# zx81_SD_12_smd_build002.net
KiCad netlist of a schematic drawn in EAGLE
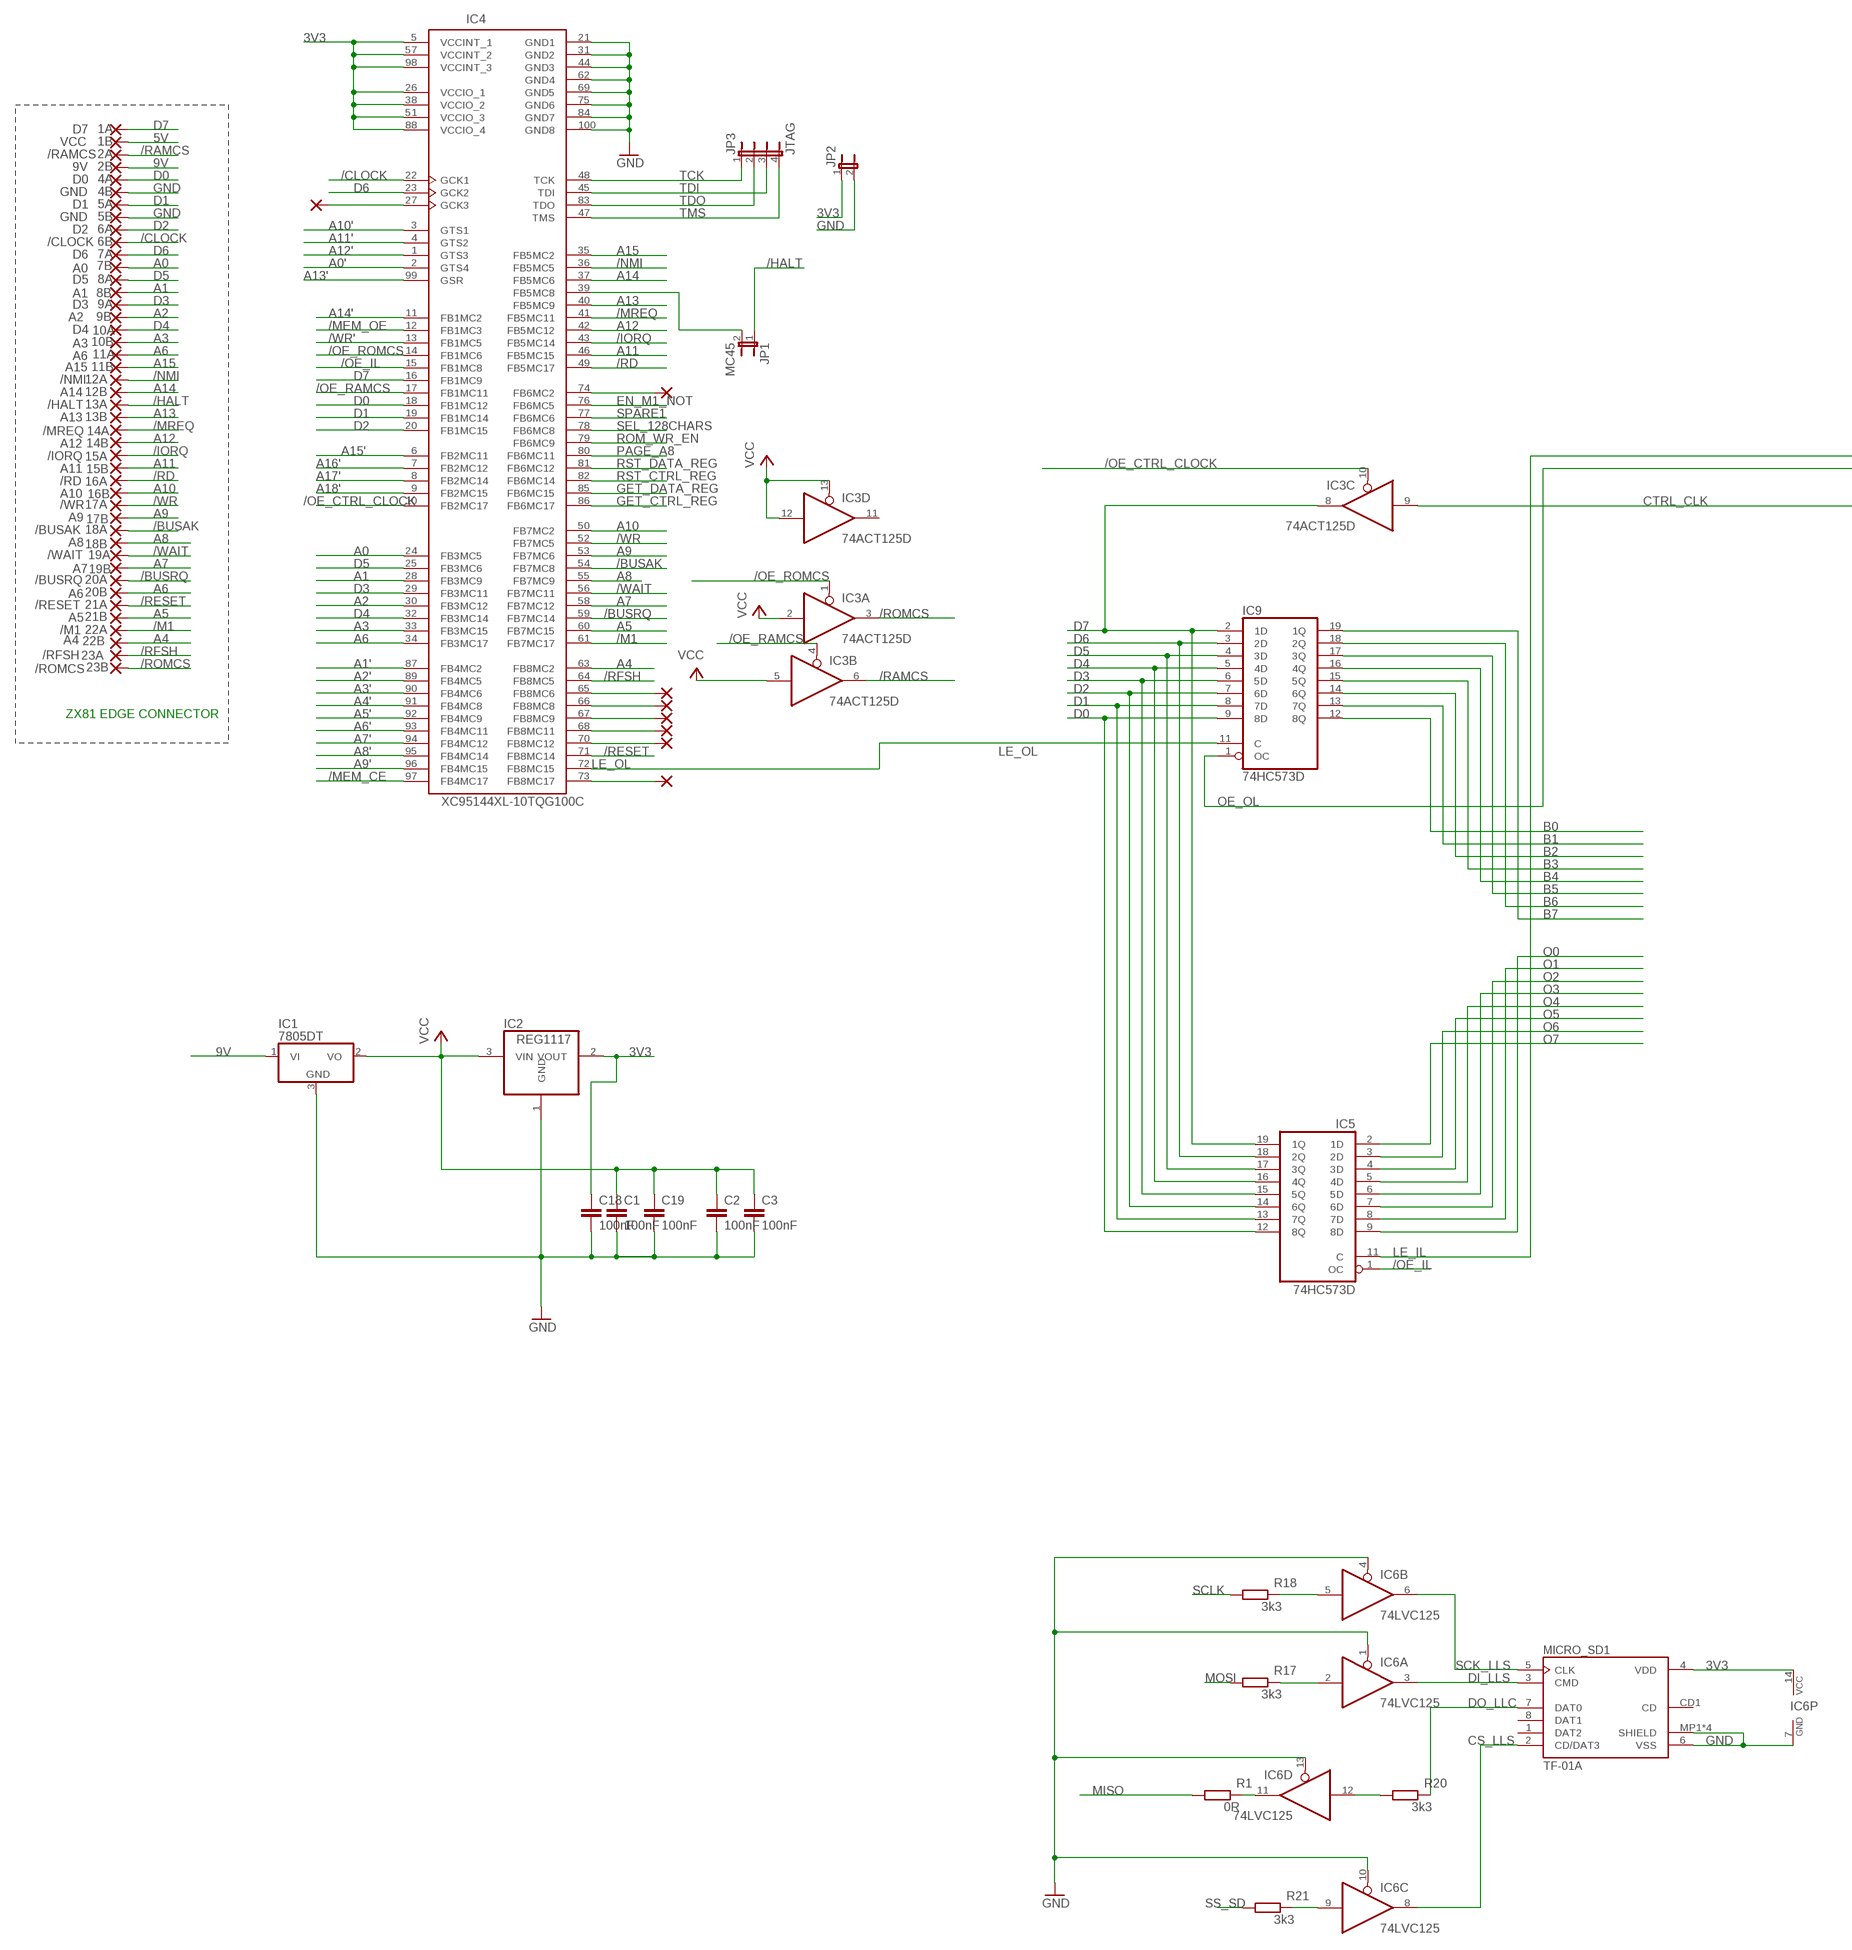
[diagram p0: schematic, sheet 1, part 1 of 2]
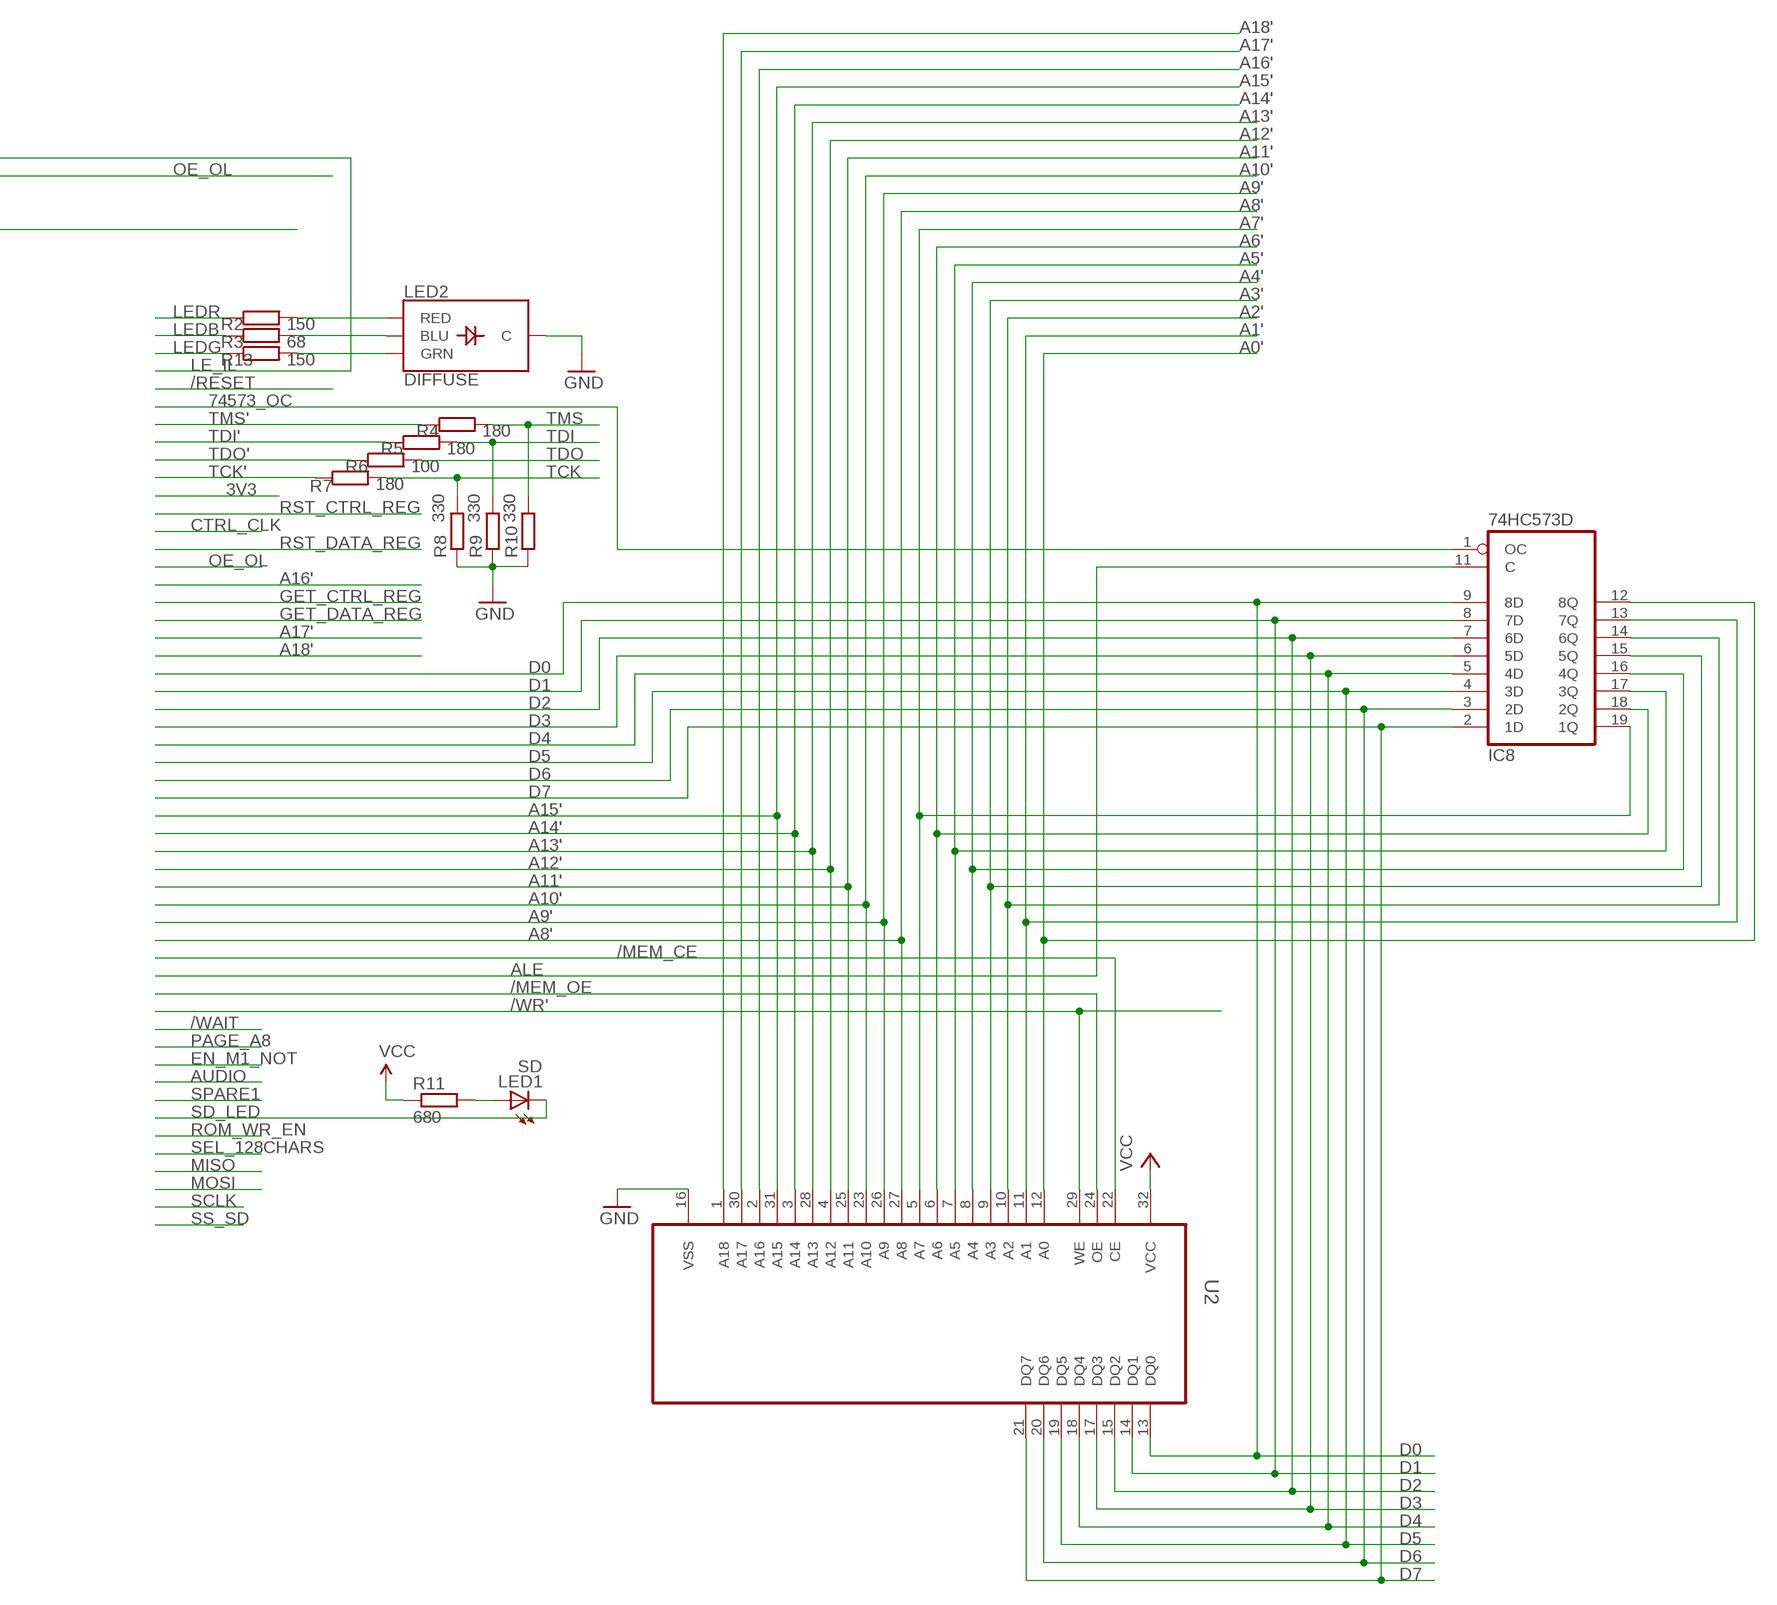
[diagram p1: schematic, sheet 1, part 2 of 2]
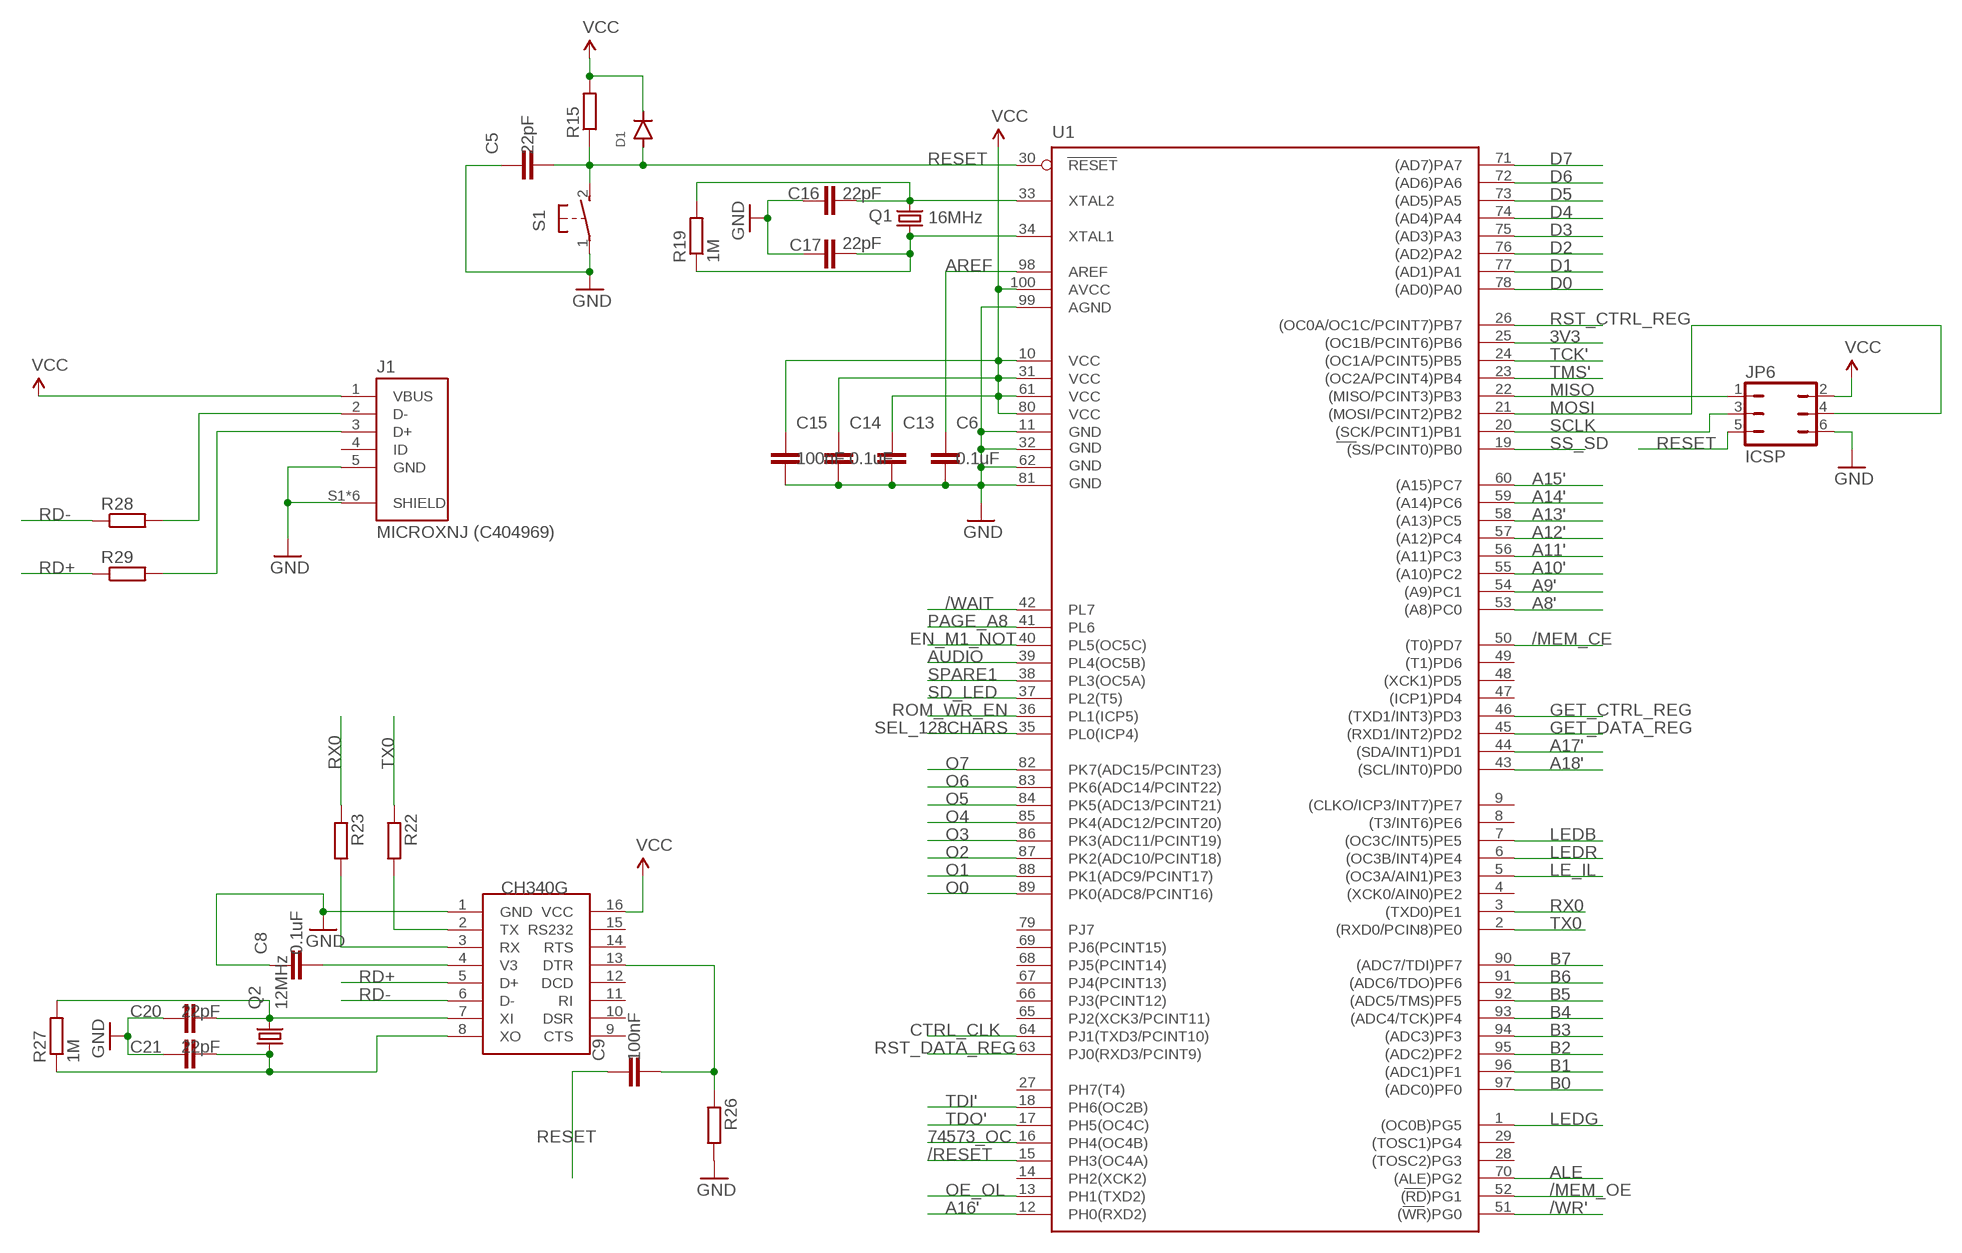
[diagram p2: schematic, sheet 2]

(export (version "E")
  (design (tool "Eeschema 10.0.6"))
  (components
    (comp (ref "C5")
      (value "22pF")
      (footprint "eagle-import:C0603")
      (libsource (lib "eagle-import") (part "C-EUC0603"))
    )
    (comp (ref "C6")
      (value "0.1uF")
      (footprint "eagle-import:C0603")
      (libsource (lib "eagle-import") (part "C-EUC0603"))
    )
    (comp (ref "C8")
      (value "0.1uF")
      (footprint "eagle-import:C0603")
      (libsource (lib "eagle-import") (part "C-EUC0603"))
    )
    (comp (ref "C9")
      (value "100nF")
      (footprint "eagle-import:C0603")
      (libsource (lib "eagle-import") (part "C-EUC0603"))
    )
    (comp (ref "C13")
      (value "0.1uF")
      (footprint "eagle-import:C0603")
      (libsource (lib "eagle-import") (part "C-EUC0603"))
    )
    (comp (ref "C14")
      (value "0.1uF")
      (footprint "eagle-import:C0603")
      (libsource (lib "eagle-import") (part "C-EUC0603"))
    )
    (comp (ref "C15")
      (value "100nF")
      (footprint "eagle-import:C0603")
      (libsource (lib "eagle-import") (part "C-EUC0603"))
    )
    (comp (ref "C16")
      (value "22pF")
      (footprint "eagle-import:C0603")
      (libsource (lib "eagle-import") (part "C-EUC0603"))
    )
    (comp (ref "C17")
      (value "22pF")
      (footprint "eagle-import:C0603")
      (libsource (lib "eagle-import") (part "C-EUC0603"))
    )
    (comp (ref "C20")
      (value "22pF")
      (footprint "eagle-import:C0603")
      (libsource (lib "eagle-import") (part "C-EUC0603"))
    )
    (comp (ref "C21")
      (value "22pF")
      (footprint "eagle-import:C0603")
      (libsource (lib "eagle-import") (part "C-EUC0603"))
    )
    (comp (ref "D1")
      (value "DIODE-SOD123")
      (footprint "eagle-import:SOD123")
      (libsource (lib "eagle-import") (part "DIODE-SOD123"))
    )
    (comp (ref "IC7")
      (value "CH340G")
      (footprint "eagle-import:SOIC16")
      (libsource (lib "eagle-import") (part "CH340G"))
    )
    (comp (ref "J1")
      (value "MICROXNJ (C404969)")
      (footprint "eagle-import:SHOUHAN_MICROXNJ")
      (fields (field (name "MF") "Shouhan") (field (name "MP") "MICROXNJ"))
      (libsource (lib "eagle-import") (part "MICROXNJ"))
    )
    (comp (ref "JP6")
      (value "ICSP")
      (footprint "eagle-import:JP3Q")
      (libsource (lib "eagle-import") (part "JP3Q"))
    )
    (comp (ref "Q1")
      (value "16MHz")
      (footprint "eagle-import:3.2X2.5_KX-7")
      (libsource (lib "eagle-import") (part "KX-7"))
    )
    (comp (ref "Q2")
      (value "12MHz")
      (footprint "eagle-import:3.2X2.5_KX-7")
      (libsource (lib "eagle-import") (part "KX-7"))
    )
    (comp (ref "R15")
      (value "R-EU_R0603")
      (footprint "eagle-import:R0603")
      (libsource (lib "eagle-import") (part "rcl_334_R-EU_R0603"))
    )
    (comp (ref "R19")
      (value "1M")
      (footprint "eagle-import:R0603")
      (libsource (lib "eagle-import") (part "rcl_334_R-EU_R0603"))
    )
    (comp (ref "R22")
      (value "1K")
      (footprint "eagle-import:R0603")
      (libsource (lib "eagle-import") (part "rcl_334_R-EU_R0603"))
    )
    (comp (ref "R23")
      (value "1K")
      (footprint "eagle-import:R0603")
      (libsource (lib "eagle-import") (part "rcl_334_R-EU_R0603"))
    )
    (comp (ref "R26")
      (value "1K")
      (footprint "eagle-import:R0603")
      (libsource (lib "eagle-import") (part "rcl_334_R-EU_R0603"))
    )
    (comp (ref "R27")
      (value "1M")
      (footprint "eagle-import:R0603")
      (libsource (lib "eagle-import") (part "rcl_334_R-EU_R0603"))
    )
    (comp (ref "R28")
      (value "22R")
      (footprint "eagle-import:R0603")
      (libsource (lib "eagle-import") (part "rcl_334_R-EU_R0603"))
    )
    (comp (ref "R29")
      (value "22R")
      (footprint "eagle-import:R0603")
      (libsource (lib "eagle-import") (part "rcl_334_R-EU_R0603"))
    )
    (comp (ref "S1")
      (value "31-XX")
      (footprint "eagle-import:B3F-31XX")
      (fields (field (name "MPN") "B3F-3100"))
      (libsource (lib "eagle-import") (part "31-XX"))
    )
    (comp (ref "U1")
      (value "ATMEGA2560AU")
      (footprint "eagle-import:TQFP100")
      (libsource (lib "eagle-import") (part "ATMEGA2560AU"))
    )
    (comp (ref "1A")
      (value "D7")
      (footprint "eagle-import:EDGEPIN")
      (libsource (lib "eagle-import") (part "SMD2EDGEPIN"))
    )
    (comp (ref "1B")
      (value "VCC")
      (footprint "eagle-import:EDGEPIN")
      (libsource (lib "eagle-import") (part "SMD2EDGEPIN"))
    )
    (comp (ref "2A")
      (value "/RAMCS")
      (footprint "eagle-import:EDGEPIN")
      (libsource (lib "eagle-import") (part "SMD2EDGEPIN"))
    )
    (comp (ref "2B")
      (value "9V")
      (footprint "eagle-import:EDGEPIN")
      (libsource (lib "eagle-import") (part "SMD2EDGEPIN"))
    )
    (comp (ref "4A")
      (value "D0")
      (footprint "eagle-import:EDGEPIN")
      (libsource (lib "eagle-import") (part "SMD2EDGEPIN"))
    )
    (comp (ref "4B")
      (value "GND")
      (footprint "eagle-import:EDGEPIN")
      (libsource (lib "eagle-import") (part "SMD2EDGEPIN"))
    )
    (comp (ref "5A")
      (value "D1")
      (footprint "eagle-import:EDGEPIN")
      (libsource (lib "eagle-import") (part "SMD2EDGEPIN"))
    )
    (comp (ref "5B")
      (value "GND")
      (footprint "eagle-import:EDGEPIN")
      (libsource (lib "eagle-import") (part "SMD2EDGEPIN"))
    )
    (comp (ref "6A")
      (value "D2")
      (footprint "eagle-import:EDGEPIN")
      (libsource (lib "eagle-import") (part "SMD2EDGEPIN"))
    )
    (comp (ref "6B")
      (value "/CLOCK")
      (footprint "eagle-import:EDGEPIN")
      (libsource (lib "eagle-import") (part "SMD2EDGEPIN"))
    )
    (comp (ref "7A")
      (value "D6")
      (footprint "eagle-import:EDGEPIN")
      (libsource (lib "eagle-import") (part "SMD2EDGEPIN"))
    )
    (comp (ref "7B")
      (value "A0")
      (footprint "eagle-import:EDGEPIN")
      (libsource (lib "eagle-import") (part "SMD2EDGEPIN"))
    )
    (comp (ref "8A")
      (value "D5")
      (footprint "eagle-import:EDGEPIN")
      (libsource (lib "eagle-import") (part "SMD2EDGEPIN"))
    )
    (comp (ref "8B")
      (value "A1")
      (footprint "eagle-import:EDGEPIN")
      (libsource (lib "eagle-import") (part "SMD2EDGEPIN"))
    )
    (comp (ref "9A")
      (value "D3")
      (footprint "eagle-import:EDGEPIN")
      (libsource (lib "eagle-import") (part "SMD2EDGEPIN"))
    )
    (comp (ref "9B")
      (value "A2")
      (footprint "eagle-import:EDGEPIN")
      (libsource (lib "eagle-import") (part "SMD2EDGEPIN"))
    )
    (comp (ref "10A")
      (value "D4")
      (footprint "eagle-import:EDGEPIN")
      (libsource (lib "eagle-import") (part "SMD2EDGEPIN"))
    )
    (comp (ref "10B")
      (value "A3")
      (footprint "eagle-import:EDGEPIN")
      (libsource (lib "eagle-import") (part "SMD2EDGEPIN"))
    )
    (comp (ref "11A")
      (value "A6")
      (footprint "eagle-import:EDGEPIN")
      (libsource (lib "eagle-import") (part "SMD2EDGEPIN"))
    )
    (comp (ref "11B")
      (value "A15")
      (footprint "eagle-import:EDGEPIN")
      (libsource (lib "eagle-import") (part "SMD2EDGEPIN"))
    )
    (comp (ref "12A")
      (value "/NMI")
      (footprint "eagle-import:EDGEPIN")
      (libsource (lib "eagle-import") (part "SMD2EDGEPIN"))
    )
    (comp (ref "12B")
      (value "A14")
      (footprint "eagle-import:EDGEPIN")
      (libsource (lib "eagle-import") (part "SMD2EDGEPIN"))
    )
    (comp (ref "13A")
      (value "/HALT")
      (footprint "eagle-import:EDGEPIN")
      (libsource (lib "eagle-import") (part "SMD2EDGEPIN"))
    )
    (comp (ref "13B")
      (value "A13")
      (footprint "eagle-import:EDGEPIN")
      (libsource (lib "eagle-import") (part "SMD2EDGEPIN"))
    )
    (comp (ref "14A")
      (value "/MREQ")
      (footprint "eagle-import:EDGEPIN")
      (libsource (lib "eagle-import") (part "SMD2EDGEPIN"))
    )
    (comp (ref "14B")
      (value "A12")
      (footprint "eagle-import:EDGEPIN")
      (libsource (lib "eagle-import") (part "SMD2EDGEPIN"))
    )
    (comp (ref "15A")
      (value "/IORQ")
      (footprint "eagle-import:EDGEPIN")
      (libsource (lib "eagle-import") (part "SMD2EDGEPIN"))
    )
    (comp (ref "15B")
      (value "A11")
      (footprint "eagle-import:EDGEPIN")
      (libsource (lib "eagle-import") (part "SMD2EDGEPIN"))
    )
    (comp (ref "16A")
      (value "/RD")
      (footprint "eagle-import:EDGEPIN")
      (libsource (lib "eagle-import") (part "SMD2EDGEPIN"))
    )
    (comp (ref "16B")
      (value "A10")
      (footprint "eagle-import:EDGEPIN")
      (libsource (lib "eagle-import") (part "SMD2EDGEPIN"))
    )
    (comp (ref "17A")
      (value "/WR")
      (footprint "eagle-import:EDGEPIN")
      (libsource (lib "eagle-import") (part "SMD2EDGEPIN"))
    )
    (comp (ref "17B")
      (value "A9")
      (footprint "eagle-import:EDGEPIN")
      (libsource (lib "eagle-import") (part "SMD2EDGEPIN"))
    )
    (comp (ref "18A")
      (value "/BUSAK")
      (footprint "eagle-import:EDGEPIN")
      (libsource (lib "eagle-import") (part "SMD2EDGEPIN"))
    )
    (comp (ref "18B")
      (value "A8")
      (footprint "eagle-import:EDGEPIN")
      (libsource (lib "eagle-import") (part "SMD2EDGEPIN"))
    )
    (comp (ref "19A")
      (value "/WAIT")
      (footprint "eagle-import:EDGEPIN")
      (libsource (lib "eagle-import") (part "SMD2EDGEPIN"))
    )
    (comp (ref "19B")
      (value "A7")
      (footprint "eagle-import:EDGEPIN")
      (libsource (lib "eagle-import") (part "SMD2EDGEPIN"))
    )
    (comp (ref "20A")
      (value "/BUSRQ")
      (footprint "eagle-import:EDGEPIN")
      (libsource (lib "eagle-import") (part "SMD2EDGEPIN"))
    )
    (comp (ref "20B")
      (value "A6")
      (footprint "eagle-import:EDGEPIN")
      (libsource (lib "eagle-import") (part "SMD2EDGEPIN"))
    )
    (comp (ref "21A")
      (value "/RESET")
      (footprint "eagle-import:EDGEPIN")
      (libsource (lib "eagle-import") (part "SMD2EDGEPIN"))
    )
    (comp (ref "21B")
      (value "A5")
      (footprint "eagle-import:EDGEPIN")
      (libsource (lib "eagle-import") (part "SMD2EDGEPIN"))
    )
    (comp (ref "22A")
      (value "/M1")
      (footprint "eagle-import:EDGEPIN")
      (libsource (lib "eagle-import") (part "SMD2EDGEPIN"))
    )
    (comp (ref "22B")
      (value "A4")
      (footprint "eagle-import:EDGEPIN")
      (libsource (lib "eagle-import") (part "SMD2EDGEPIN"))
    )
    (comp (ref "23A")
      (value "/RFSH")
      (footprint "eagle-import:EDGEPIN")
      (libsource (lib "eagle-import") (part "SMD2EDGEPIN"))
    )
    (comp (ref "23B")
      (value "/ROMCS")
      (footprint "eagle-import:EDGEPIN")
      (libsource (lib "eagle-import") (part "SMD2EDGEPIN"))
    )
    (comp (ref "C1")
      (value "100nF")
      (footprint "eagle-import:C0603")
      (libsource (lib "eagle-import") (part "C-EUC0603"))
    )
    (comp (ref "C2")
      (value "100nF")
      (footprint "eagle-import:C0603")
      (libsource (lib "eagle-import") (part "C-EUC0603"))
    )
    (comp (ref "C3")
      (value "100nF")
      (footprint "eagle-import:C0603")
      (libsource (lib "eagle-import") (part "C-EUC0603"))
    )
    (comp (ref "C18")
      (value "100nF")
      (footprint "eagle-import:C0603")
      (libsource (lib "eagle-import") (part "C-EUC0603"))
    )
    (comp (ref "C19")
      (value "100nF")
      (footprint "eagle-import:C0603")
      (libsource (lib "eagle-import") (part "C-EUC0603"))
    )
    (comp (ref "IC1")
      (value "7805DT")
      (footprint "eagle-import:TO252")
      (libsource (lib "eagle-import") (part "78DT05"))
    )
    (comp (ref "IC2")
      (value "REG1117")
      (footprint "eagle-import:SOT223")
      (libsource (lib "eagle-import") (part "REG1117"))
    )
    (comp (ref "IC3")
      (value "74ACT125D")
      (footprint "eagle-import:SO14")
      (libsource (lib "eagle-import") (part "74125DACT"))
    )
    (comp (ref "IC4")
      (value "XC95144XL-10TQG100C")
      (footprint "eagle-import:TQFP100")
      (fields (field (name "MF") "Xilinx Inc."))
      (libsource (lib "eagle-import") (part "XC95144XL-10TQG100C"))
    )
    (comp (ref "IC5")
      (value "74HC573D")
      (footprint "eagle-import:SO20W")
      (libsource (lib "eagle-import") (part "74573DHC"))
    )
    (comp (ref "IC6")
      (value "74LVC125")
      (footprint "eagle-import:SO14")
      (libsource (lib "eagle-import") (part "74125DLS"))
    )
    (comp (ref "IC8")
      (value "74HC573D")
      (footprint "eagle-import:SO20W")
      (libsource (lib "eagle-import") (part "74573DHC"))
    )
    (comp (ref "IC9")
      (value "74HC573D")
      (footprint "eagle-import:SO20W")
      (libsource (lib "eagle-import") (part "74573DHC"))
    )
    (comp (ref "JP1")
      (value "MC45")
      (footprint "eagle-import:JP1")
      (libsource (lib "eagle-import") (part "JP1E"))
    )
    (comp (ref "JP2")
      (value "JP1E")
      (footprint "eagle-import:JP1")
      (libsource (lib "eagle-import") (part "JP1E"))
    )
    (comp (ref "JP3")
      (value "JTAG")
      (footprint "eagle-import:JP4")
      (libsource (lib "eagle-import") (part "JP4E"))
    )
    (comp (ref "LED1")
      (value "SD")
      (footprint "eagle-import:LED5MM")
      (libsource (lib "eagle-import") (part "LED5MM"))
    )
    (comp (ref "LED2")
      (value "DIFFUSE")
      (footprint "eagle-import:LED-RGB-THRU")
      (libsource (lib "eagle-import") (part "LED-RGB-CCDIFFUSE"))
    )
    (comp (ref "MICRO_SD1")
      (value "TF-01A")
      (footprint "eagle-import:TF-01A")
      (fields (field (name "MF") "HRO Electronics Co., Ltd."))
      (libsource (lib "eagle-import") (part "TF-01A"))
    )
    (comp (ref "PAD1")
      (value "1,6/0,8")
      (footprint "eagle-import:1,6_0,8")
      (libsource (lib "eagle-import") (part "1,6/0,8"))
    )
    (comp (ref "PAD2")
      (value "1,6/0,8")
      (footprint "eagle-import:1,6_0,8")
      (libsource (lib "eagle-import") (part "1,6/0,8"))
    )
    (comp (ref "PAD3")
      (value "1,6/0,8")
      (footprint "eagle-import:1,6_0,8")
      (libsource (lib "eagle-import") (part "1,6/0,8"))
    )
    (comp (ref "PAD4")
      (value "1,6/0,8")
      (footprint "eagle-import:1,6_0,8")
      (libsource (lib "eagle-import") (part "1,6/0,8"))
    )
    (comp (ref "PAD5")
      (value "1,6/0,8")
      (footprint "eagle-import:1,6_0,8")
      (libsource (lib "eagle-import") (part "1,6/0,8"))
    )
    (comp (ref "PAD6")
      (value "1,6/0,8")
      (footprint "eagle-import:1,6_0,8")
      (libsource (lib "eagle-import") (part "1,6/0,8"))
    )
    (comp (ref "PAD7")
      (value "1,6/0,8")
      (footprint "eagle-import:1,6_0,8")
      (libsource (lib "eagle-import") (part "1,6/0,8"))
    )
    (comp (ref "PAD8")
      (value "1,6/0,8")
      (footprint "eagle-import:1,6_0,8")
      (libsource (lib "eagle-import") (part "1,6/0,8"))
    )
    (comp (ref "R1")
      (value "0R")
      (footprint "eagle-import:R0603")
      (libsource (lib "eagle-import") (part "R-EU_R0603"))
    )
    (comp (ref "R2")
      (value "150")
      (footprint "eagle-import:R0603")
      (libsource (lib "eagle-import") (part "rcl_334_R-EU_R0603"))
    )
    (comp (ref "R3")
      (value "68")
      (footprint "eagle-import:R0603")
      (libsource (lib "eagle-import") (part "rcl_334_R-EU_R0603"))
    )
    (comp (ref "R4")
      (value "180")
      (footprint "eagle-import:R0603")
      (libsource (lib "eagle-import") (part "rcl_334_R-EU_R0603"))
    )
    (comp (ref "R5")
      (value "180")
      (footprint "eagle-import:R0603")
      (libsource (lib "eagle-import") (part "rcl_334_R-EU_R0603"))
    )
    (comp (ref "R6")
      (value "100")
      (footprint "eagle-import:R0603")
      (libsource (lib "eagle-import") (part "rcl_334_R-EU_R0603"))
    )
    (comp (ref "R7")
      (value "180")
      (footprint "eagle-import:R0603")
      (libsource (lib "eagle-import") (part "rcl_334_R-EU_R0603"))
    )
    (comp (ref "R8")
      (value "330")
      (footprint "eagle-import:R0603")
      (libsource (lib "eagle-import") (part "rcl_334_R-EU_R0603"))
    )
    (comp (ref "R9")
      (value "330")
      (footprint "eagle-import:R0603")
      (libsource (lib "eagle-import") (part "rcl_334_R-EU_R0603"))
    )
    (comp (ref "R10")
      (value "330")
      (footprint "eagle-import:R0603")
      (libsource (lib "eagle-import") (part "rcl_334_R-EU_R0603"))
    )
    (comp (ref "R11")
      (value "680")
      (footprint "eagle-import:R0603")
      (libsource (lib "eagle-import") (part "R-EU_R0603"))
    )
    (comp (ref "R13")
      (value "150")
      (footprint "eagle-import:R0603")
      (libsource (lib "eagle-import") (part "rcl_334_R-EU_R0603"))
    )
    (comp (ref "R17")
      (value "3k3")
      (footprint "eagle-import:R0603")
      (libsource (lib "eagle-import") (part "R-EU_R0603"))
    )
    (comp (ref "R18")
      (value "3k3")
      (footprint "eagle-import:R0603")
      (libsource (lib "eagle-import") (part "R-EU_R0603"))
    )
    (comp (ref "R20")
      (value "3k3")
      (footprint "eagle-import:R0603")
      (libsource (lib "eagle-import") (part "R-EU_R0603"))
    )
    (comp (ref "R21")
      (value "3k3")
      (footprint "eagle-import:R0603")
      (libsource (lib "eagle-import") (part "R-EU_R0603"))
    )
    (comp (ref "U2")
      (value "AS6C4008-55SINSOP5")
      (footprint "eagle-import:SOP32-5")
      (libsource (lib "eagle-import") (part "AS6C4008-55SINSOP5"))
    )
  )
  (nets
    (net (code "1") (name "3V3") (class "Default")
      (node (ref "C18") (pin "1") (pinfunction "1_1") (pintype "passive"))
      (node (ref "IC2") (pin "2") (pinfunction "VOUT_2") (pintype "output"))
      (node (ref "IC4") (pin "26") (pinfunction "VCCIO_1_26") (pintype "power_in"))
      (node (ref "IC4") (pin "38") (pinfunction "VCCIO_2_38") (pintype "power_in"))
      (node (ref "IC4") (pin "5") (pinfunction "VCCINT_1_5") (pintype "power_in"))
      (node (ref "IC4") (pin "51") (pinfunction "VCCIO_3_51") (pintype "power_in"))
      (node (ref "IC4") (pin "57") (pinfunction "VCCINT_2_57") (pintype "power_in"))
      (node (ref "IC4") (pin "88") (pinfunction "VCCIO_4_88") (pintype "power_in"))
      (node (ref "IC4") (pin "98") (pinfunction "VCCINT_3_98") (pintype "power_in"))
      (node (ref "IC6") (pin "14") (pinfunction "VCC_14") (pintype "power_in"))
      (node (ref "JP2") (pin "1") (pinfunction "1_1") (pintype "passive"))
      (node (ref "MICRO_SD1") (pin "4") (pinfunction "VDD_4") (pintype "power_in"))
      (node (ref "U1") (pin "25") (pinfunction "(OC1B/PCINT6)PB6_25") (pintype "bidirectional"))
    )
    (net (code "2") (name "5V") (class "Default")
      (node (ref "1B") (pin "1") (pinfunction "P_1") (pintype "passive"))
    )
    (net (code "3") (name "9V") (class "Default")
      (node (ref "2B") (pin "1") (pinfunction "P_1") (pintype "passive"))
      (node (ref "IC1") (pin "1") (pinfunction "VI_1") (pintype "input"))
    )
    (net (code "4") (name "74573_OC") (class "Default")
      (node (ref "IC8") (pin "1") (pinfunction "OC_1") (pintype "input"))
      (node (ref "U1") (pin "16") (pinfunction "PH4(OC4B)_16") (pintype "bidirectional"))
    )
    (net (code "5") (name "A0") (class "Default")
      (node (ref "7B") (pin "1") (pinfunction "P_1") (pintype "passive"))
      (node (ref "IC4") (pin "24") (pinfunction "FB3MC5_24") (pintype "bidirectional"))
    )
    (net (code "6") (name "A0'") (class "Default")
      (node (ref "IC4") (pin "2") (pinfunction "GTS4_2") (pintype "bidirectional"))
      (node (ref "IC8") (pin "12") (pinfunction "8Q_12") (pintype "tri_state"))
      (node (ref "U2") (pin "12") (pinfunction "A0_12") (pintype "input"))
    )
    (net (code "7") (name "A1") (class "Default")
      (node (ref "8B") (pin "1") (pinfunction "P_1") (pintype "passive"))
      (node (ref "IC4") (pin "28") (pinfunction "FB3MC9_28") (pintype "bidirectional"))
    )
    (net (code "8") (name "A1'") (class "Default")
      (node (ref "IC4") (pin "87") (pinfunction "FB4MC2_87") (pintype "bidirectional"))
      (node (ref "IC8") (pin "13") (pinfunction "7Q_13") (pintype "tri_state"))
      (node (ref "U2") (pin "11") (pinfunction "A1_11") (pintype "input"))
    )
    (net (code "9") (name "A2") (class "Default")
      (node (ref "9B") (pin "1") (pinfunction "P_1") (pintype "passive"))
      (node (ref "IC4") (pin "30") (pinfunction "FB3MC12_30") (pintype "bidirectional"))
    )
    (net (code "10") (name "A2'") (class "Default")
      (node (ref "IC4") (pin "89") (pinfunction "FB4MC5_89") (pintype "bidirectional"))
      (node (ref "IC8") (pin "14") (pinfunction "6Q_14") (pintype "tri_state"))
      (node (ref "U2") (pin "10") (pinfunction "A2_10") (pintype "input"))
    )
    (net (code "11") (name "A3") (class "Default")
      (node (ref "10B") (pin "1") (pinfunction "P_1") (pintype "passive"))
      (node (ref "IC4") (pin "33") (pinfunction "FB3MC15_33") (pintype "bidirectional"))
    )
    (net (code "12") (name "A3'") (class "Default")
      (node (ref "IC4") (pin "90") (pinfunction "FB4MC6_90") (pintype "bidirectional"))
      (node (ref "IC8") (pin "15") (pinfunction "5Q_15") (pintype "tri_state"))
      (node (ref "U2") (pin "9") (pinfunction "A3_9") (pintype "input"))
    )
    (net (code "13") (name "A4") (class "Default")
      (node (ref "22B") (pin "1") (pinfunction "P_1") (pintype "passive"))
      (node (ref "IC4") (pin "63") (pinfunction "FB8MC2_63") (pintype "bidirectional"))
    )
    (net (code "14") (name "A4'") (class "Default")
      (node (ref "IC4") (pin "91") (pinfunction "FB4MC8_91") (pintype "bidirectional"))
      (node (ref "IC8") (pin "16") (pinfunction "4Q_16") (pintype "tri_state"))
      (node (ref "U2") (pin "8") (pinfunction "A4_8") (pintype "input"))
    )
    (net (code "15") (name "A5") (class "Default")
      (node (ref "21B") (pin "1") (pinfunction "P_1") (pintype "passive"))
      (node (ref "IC4") (pin "60") (pinfunction "FB7MC15_60") (pintype "bidirectional"))
    )
    (net (code "16") (name "A5'") (class "Default")
      (node (ref "IC4") (pin "92") (pinfunction "FB4MC9_92") (pintype "bidirectional"))
      (node (ref "IC8") (pin "17") (pinfunction "3Q_17") (pintype "tri_state"))
      (node (ref "U2") (pin "7") (pinfunction "A5_7") (pintype "input"))
    )
    (net (code "17") (name "A6") (class "Default")
      (node (ref "11A") (pin "1") (pinfunction "P_1") (pintype "passive"))
      (node (ref "20B") (pin "1") (pinfunction "P_1") (pintype "passive"))
      (node (ref "IC4") (pin "34") (pinfunction "FB3MC17_34") (pintype "bidirectional"))
    )
    (net (code "18") (name "A6'") (class "Default")
      (node (ref "IC4") (pin "93") (pinfunction "FB4MC11_93") (pintype "bidirectional"))
      (node (ref "IC8") (pin "18") (pinfunction "2Q_18") (pintype "tri_state"))
      (node (ref "U2") (pin "6") (pinfunction "A6_6") (pintype "input"))
    )
    (net (code "19") (name "A7") (class "Default")
      (node (ref "19B") (pin "1") (pinfunction "P_1") (pintype "passive"))
      (node (ref "IC4") (pin "58") (pinfunction "FB7MC12_58") (pintype "bidirectional"))
    )
    (net (code "20") (name "A7'") (class "Default")
      (node (ref "IC4") (pin "94") (pinfunction "FB4MC12_94") (pintype "bidirectional"))
      (node (ref "IC8") (pin "19") (pinfunction "1Q_19") (pintype "tri_state"))
      (node (ref "U2") (pin "5") (pinfunction "A7_5") (pintype "input"))
    )
    (net (code "21") (name "A8") (class "Default")
      (node (ref "18B") (pin "1") (pinfunction "P_1") (pintype "passive"))
      (node (ref "IC4") (pin "55") (pinfunction "FB7MC9_55") (pintype "bidirectional"))
    )
    (net (code "22") (name "A8'") (class "Default")
      (node (ref "IC4") (pin "95") (pinfunction "FB4MC14_95") (pintype "bidirectional"))
      (node (ref "U1") (pin "53") (pinfunction "(A8)PC0_53") (pintype "bidirectional"))
      (node (ref "U2") (pin "27") (pinfunction "A8_27") (pintype "input"))
    )
    (net (code "23") (name "A9") (class "Default")
      (node (ref "17B") (pin "1") (pinfunction "P_1") (pintype "passive"))
      (node (ref "IC4") (pin "53") (pinfunction "FB7MC6_53") (pintype "bidirectional"))
    )
    (net (code "24") (name "A9'") (class "Default")
      (node (ref "IC4") (pin "96") (pinfunction "FB4MC15_96") (pintype "bidirectional"))
      (node (ref "U1") (pin "54") (pinfunction "(A9)PC1_54") (pintype "bidirectional"))
      (node (ref "U2") (pin "26") (pinfunction "A9_26") (pintype "input"))
    )
    (net (code "25") (name "A10") (class "Default")
      (node (ref "16B") (pin "1") (pinfunction "P_1") (pintype "passive"))
      (node (ref "IC4") (pin "50") (pinfunction "FB7MC2_50") (pintype "bidirectional"))
    )
    (net (code "26") (name "A10'") (class "Default")
      (node (ref "IC4") (pin "3") (pinfunction "GTS1_3") (pintype "bidirectional"))
      (node (ref "U1") (pin "55") (pinfunction "(A10)PC2_55") (pintype "bidirectional"))
      (node (ref "U2") (pin "23") (pinfunction "A10_23") (pintype "input"))
    )
    (net (code "27") (name "A11") (class "Default")
      (node (ref "15B") (pin "1") (pinfunction "P_1") (pintype "passive"))
      (node (ref "IC4") (pin "46") (pinfunction "FB5MC15_46") (pintype "bidirectional"))
    )
    (net (code "28") (name "A11'") (class "Default")
      (node (ref "IC4") (pin "4") (pinfunction "GTS2_4") (pintype "bidirectional"))
      (node (ref "U1") (pin "56") (pinfunction "(A11)PC3_56") (pintype "bidirectional"))
      (node (ref "U2") (pin "25") (pinfunction "A11_25") (pintype "input"))
    )
    (net (code "29") (name "A12") (class "Default")
      (node (ref "14B") (pin "1") (pinfunction "P_1") (pintype "passive"))
      (node (ref "IC4") (pin "42") (pinfunction "FB5MC12_42") (pintype "bidirectional"))
    )
    (net (code "30") (name "A12'") (class "Default")
      (node (ref "IC4") (pin "1") (pinfunction "GTS3_1") (pintype "bidirectional"))
      (node (ref "U1") (pin "57") (pinfunction "(A12)PC4_57") (pintype "bidirectional"))
      (node (ref "U2") (pin "4") (pinfunction "A12_4") (pintype "input"))
    )
    (net (code "31") (name "A13") (class "Default")
      (node (ref "13B") (pin "1") (pinfunction "P_1") (pintype "passive"))
      (node (ref "IC4") (pin "40") (pinfunction "FB5MC9_40") (pintype "bidirectional"))
    )
    (net (code "32") (name "A13'") (class "Default")
      (node (ref "IC4") (pin "99") (pinfunction "GSR_99") (pintype "bidirectional"))
      (node (ref "U1") (pin "58") (pinfunction "(A13)PC5_58") (pintype "bidirectional"))
      (node (ref "U2") (pin "28") (pinfunction "A13_28") (pintype "input"))
    )
    (net (code "33") (name "A14") (class "Default")
      (node (ref "12B") (pin "1") (pinfunction "P_1") (pintype "passive"))
      (node (ref "IC4") (pin "37") (pinfunction "FB5MC6_37") (pintype "bidirectional"))
    )
    (net (code "34") (name "A14'") (class "Default")
      (node (ref "IC4") (pin "11") (pinfunction "FB1MC2_11") (pintype "bidirectional"))
      (node (ref "U1") (pin "59") (pinfunction "(A14)PC6_59") (pintype "bidirectional"))
      (node (ref "U2") (pin "3") (pinfunction "A14_3") (pintype "input"))
    )
    (net (code "35") (name "A15") (class "Default")
      (node (ref "11B") (pin "1") (pinfunction "P_1") (pintype "passive"))
      (node (ref "IC4") (pin "35") (pinfunction "FB5MC2_35") (pintype "bidirectional"))
    )
    (net (code "36") (name "A15'") (class "Default")
      (node (ref "IC4") (pin "6") (pinfunction "FB2MC11_6") (pintype "bidirectional"))
      (node (ref "U1") (pin "60") (pinfunction "(A15)PC7_60") (pintype "bidirectional"))
      (node (ref "U2") (pin "31") (pinfunction "A15_31") (pintype "input"))
    )
    (net (code "37") (name "A16'") (class "Default")
      (node (ref "IC4") (pin "7") (pinfunction "FB2MC12_7") (pintype "bidirectional"))
      (node (ref "U1") (pin "12") (pinfunction "PH0(RXD2)_12") (pintype "bidirectional"))
      (node (ref "U2") (pin "2") (pinfunction "A16_2") (pintype "input"))
    )
    (net (code "38") (name "A17'") (class "Default")
      (node (ref "IC4") (pin "8") (pinfunction "FB2MC14_8") (pintype "bidirectional"))
      (node (ref "U1") (pin "44") (pinfunction "(SDA/INT1)PD1_44") (pintype "bidirectional"))
      (node (ref "U2") (pin "30") (pinfunction "A17_30") (pintype "input"))
    )
    (net (code "39") (name "A18'") (class "Default")
      (node (ref "IC4") (pin "9") (pinfunction "FB2MC15_9") (pintype "bidirectional"))
      (node (ref "U1") (pin "43") (pinfunction "(SCL/INT0)PD0_43") (pintype "bidirectional"))
      (node (ref "U2") (pin "1") (pinfunction "A18_1") (pintype "input"))
    )
    (net (code "40") (name "ALE") (class "Default")
      (node (ref "IC8") (pin "11") (pinfunction "C_11") (pintype "input"))
      (node (ref "U1") (pin "70") (pinfunction "(ALE)PG2_70") (pintype "bidirectional"))
    )
    (net (code "41") (name "AREF") (class "Default")
      (node (ref "C6") (pin "1") (pinfunction "1_1") (pintype "passive"))
      (node (ref "U1") (pin "98") (pinfunction "AREF_98") (pintype "bidirectional"))
    )
    (net (code "42") (name "AUDIO") (class "Default")
      (node (ref "U1") (pin "39") (pinfunction "PL4(OC5B)_39") (pintype "bidirectional"))
    )
    (net (code "43") (name "B0") (class "Default")
      (node (ref "IC9") (pin "19") (pinfunction "1Q_19") (pintype "tri_state"))
      (node (ref "U1") (pin "97") (pinfunction "(ADC0)PF0_97") (pintype "bidirectional"))
    )
    (net (code "44") (name "B1") (class "Default")
      (node (ref "IC9") (pin "18") (pinfunction "2Q_18") (pintype "tri_state"))
      (node (ref "U1") (pin "96") (pinfunction "(ADC1)PF1_96") (pintype "bidirectional"))
    )
    (net (code "45") (name "B2") (class "Default")
      (node (ref "IC9") (pin "17") (pinfunction "3Q_17") (pintype "tri_state"))
      (node (ref "U1") (pin "95") (pinfunction "(ADC2)PF2_95") (pintype "bidirectional"))
    )
    (net (code "46") (name "B3") (class "Default")
      (node (ref "IC9") (pin "16") (pinfunction "4Q_16") (pintype "tri_state"))
      (node (ref "U1") (pin "94") (pinfunction "(ADC3)PF3_94") (pintype "bidirectional"))
    )
    (net (code "47") (name "B4") (class "Default")
      (node (ref "IC9") (pin "15") (pinfunction "5Q_15") (pintype "tri_state"))
      (node (ref "U1") (pin "93") (pinfunction "(ADC4/TCK)PF4_93") (pintype "bidirectional"))
    )
    (net (code "48") (name "B5") (class "Default")
      (node (ref "IC9") (pin "14") (pinfunction "6Q_14") (pintype "tri_state"))
      (node (ref "U1") (pin "92") (pinfunction "(ADC5/TMS)PF5_92") (pintype "bidirectional"))
    )
    (net (code "49") (name "B6") (class "Default")
      (node (ref "IC9") (pin "13") (pinfunction "7Q_13") (pintype "tri_state"))
      (node (ref "U1") (pin "91") (pinfunction "(ADC6/TDO)PF6_91") (pintype "bidirectional"))
    )
    (net (code "50") (name "B7") (class "Default")
      (node (ref "IC9") (pin "12") (pinfunction "8Q_12") (pintype "tri_state"))
      (node (ref "U1") (pin "90") (pinfunction "(ADC7/TDI)PF7_90") (pintype "bidirectional"))
    )
    (net (code "51") (name "CS_LLS") (class "Default")
      (node (ref "IC6") (pin "8") (pinfunction "O_8") (pintype "tri_state"))
      (node (ref "MICRO_SD1") (pin "2") (pinfunction "CD/DAT3_2") (pintype "bidirectional"))
    )
    (net (code "52") (name "CTRL_CLK") (class "Default")
      (node (ref "IC3") (pin "9") (pinfunction "I_9") (pintype "input"))
      (node (ref "U1") (pin "64") (pinfunction "PJ1(TXD3/PCINT10)_64") (pintype "bidirectional"))
    )
    (net (code "53") (name "D0") (class "Default")
      (node (ref "4A") (pin "1") (pinfunction "P_1") (pintype "passive"))
      (node (ref "IC4") (pin "18") (pinfunction "FB1MC12_18") (pintype "bidirectional"))
      (node (ref "IC5") (pin "12") (pinfunction "8Q_12") (pintype "tri_state"))
      (node (ref "IC8") (pin "9") (pinfunction "8D_9") (pintype "input"))
      (node (ref "IC9") (pin "9") (pinfunction "8D_9") (pintype "input"))
      (node (ref "U1") (pin "78") (pinfunction "(AD0)PA0_78") (pintype "bidirectional"))
      (node (ref "U2") (pin "13") (pinfunction "DQ0_13") (pintype "output"))
    )
    (net (code "54") (name "D1") (class "Default")
      (node (ref "5A") (pin "1") (pinfunction "P_1") (pintype "passive"))
      (node (ref "IC4") (pin "19") (pinfunction "FB1MC14_19") (pintype "bidirectional"))
      (node (ref "IC5") (pin "13") (pinfunction "7Q_13") (pintype "tri_state"))
      (node (ref "IC8") (pin "8") (pinfunction "7D_8") (pintype "input"))
      (node (ref "IC9") (pin "8") (pinfunction "7D_8") (pintype "input"))
      (node (ref "U1") (pin "77") (pinfunction "(AD1)PA1_77") (pintype "bidirectional"))
      (node (ref "U2") (pin "14") (pinfunction "DQ1_14") (pintype "output"))
    )
    (net (code "55") (name "D2") (class "Default")
      (node (ref "6A") (pin "1") (pinfunction "P_1") (pintype "passive"))
      (node (ref "IC4") (pin "20") (pinfunction "FB1MC15_20") (pintype "bidirectional"))
      (node (ref "IC5") (pin "14") (pinfunction "6Q_14") (pintype "tri_state"))
      (node (ref "IC8") (pin "7") (pinfunction "6D_7") (pintype "input"))
      (node (ref "IC9") (pin "7") (pinfunction "6D_7") (pintype "input"))
      (node (ref "U1") (pin "76") (pinfunction "(AD2)PA2_76") (pintype "bidirectional"))
      (node (ref "U2") (pin "15") (pinfunction "DQ2_15") (pintype "output"))
    )
    (net (code "56") (name "D3") (class "Default")
      (node (ref "9A") (pin "1") (pinfunction "P_1") (pintype "passive"))
      (node (ref "IC4") (pin "29") (pinfunction "FB3MC11_29") (pintype "bidirectional"))
      (node (ref "IC5") (pin "15") (pinfunction "5Q_15") (pintype "tri_state"))
      (node (ref "IC8") (pin "6") (pinfunction "5D_6") (pintype "input"))
      (node (ref "IC9") (pin "6") (pinfunction "5D_6") (pintype "input"))
      (node (ref "U1") (pin "75") (pinfunction "(AD3)PA3_75") (pintype "bidirectional"))
      (node (ref "U2") (pin "17") (pinfunction "DQ3_17") (pintype "output"))
    )
    (net (code "57") (name "D4") (class "Default")
      (node (ref "10A") (pin "1") (pinfunction "P_1") (pintype "passive"))
      (node (ref "IC4") (pin "32") (pinfunction "FB3MC14_32") (pintype "bidirectional"))
      (node (ref "IC5") (pin "16") (pinfunction "4Q_16") (pintype "tri_state"))
      (node (ref "IC8") (pin "5") (pinfunction "4D_5") (pintype "input"))
      (node (ref "IC9") (pin "5") (pinfunction "4D_5") (pintype "input"))
      (node (ref "U1") (pin "74") (pinfunction "(AD4)PA4_74") (pintype "bidirectional"))
      (node (ref "U2") (pin "18") (pinfunction "DQ4_18") (pintype "output"))
    )
    (net (code "58") (name "D5") (class "Default")
      (node (ref "8A") (pin "1") (pinfunction "P_1") (pintype "passive"))
      (node (ref "IC4") (pin "25") (pinfunction "FB3MC6_25") (pintype "bidirectional"))
      (node (ref "IC5") (pin "17") (pinfunction "3Q_17") (pintype "tri_state"))
      (node (ref "IC8") (pin "4") (pinfunction "3D_4") (pintype "input"))
      (node (ref "IC9") (pin "4") (pinfunction "3D_4") (pintype "input"))
      (node (ref "U1") (pin "73") (pinfunction "(AD5)PA5_73") (pintype "bidirectional"))
      (node (ref "U2") (pin "19") (pinfunction "DQ5_19") (pintype "output"))
    )
    (net (code "59") (name "D6") (class "Default")
      (node (ref "7A") (pin "1") (pinfunction "P_1") (pintype "passive"))
      (node (ref "IC4") (pin "23") (pinfunction "GCK2_23") (pintype "bidirectional"))
      (node (ref "IC5") (pin "18") (pinfunction "2Q_18") (pintype "tri_state"))
      (node (ref "IC8") (pin "3") (pinfunction "2D_3") (pintype "input"))
      (node (ref "IC9") (pin "3") (pinfunction "2D_3") (pintype "input"))
      (node (ref "U1") (pin "72") (pinfunction "(AD6)PA6_72") (pintype "bidirectional"))
      (node (ref "U2") (pin "20") (pinfunction "DQ6_20") (pintype "output"))
    )
    (net (code "60") (name "D7") (class "Default")
      (node (ref "1A") (pin "1") (pinfunction "P_1") (pintype "passive"))
      (node (ref "IC3") (pin "8") (pinfunction "O_8") (pintype "tri_state"))
      (node (ref "IC4") (pin "16") (pinfunction "FB1MC9_16") (pintype "bidirectional"))
      (node (ref "IC5") (pin "19") (pinfunction "1Q_19") (pintype "tri_state"))
      (node (ref "IC8") (pin "2") (pinfunction "1D_2") (pintype "input"))
      (node (ref "IC9") (pin "2") (pinfunction "1D_2") (pintype "input"))
      (node (ref "U1") (pin "71") (pinfunction "(AD7)PA7_71") (pintype "bidirectional"))
      (node (ref "U2") (pin "21") (pinfunction "DQ7_21") (pintype "output"))
    )
    (net (code "61") (name "DI_LLS") (class "Default")
      (node (ref "IC6") (pin "3") (pinfunction "O_3") (pintype "tri_state"))
      (node (ref "MICRO_SD1") (pin "3") (pinfunction "CMD_3") (pintype "bidirectional"))
    )
    (net (code "62") (name "DO_LLC") (class "Default")
      (node (ref "IC6") (pin "12") (pinfunction "I_12") (pintype "input"))
      (node (ref "R20") (pin "1") (pinfunction "1_1") (pintype "passive"))
    )
    (net (code "63") (name "EN_M1_NOT") (class "Default")
      (node (ref "IC4") (pin "76") (pinfunction "FB6MC5_76") (pintype "bidirectional"))
      (node (ref "U1") (pin "40") (pinfunction "PL5(OC5C)_40") (pintype "bidirectional"))
    )
    (net (code "64") (name "GET_CTRL_REG") (class "Default")
      (node (ref "IC4") (pin "86") (pinfunction "FB6MC17_86") (pintype "bidirectional"))
      (node (ref "U1") (pin "46") (pinfunction "(TXD1/INT3)PD3_46") (pintype "bidirectional"))
    )
    (net (code "65") (name "GET_DATA_REG") (class "Default")
      (node (ref "IC4") (pin "85") (pinfunction "FB6MC15_85") (pintype "bidirectional"))
      (node (ref "U1") (pin "45") (pinfunction "(RXD1/INT2)PD2_45") (pintype "bidirectional"))
    )
    (net (code "66") (name "GND") (class "Default")
      (node (ref "4B") (pin "1") (pinfunction "P_1") (pintype "passive"))
      (node (ref "5B") (pin "1") (pinfunction "P_1") (pintype "passive"))
      (node (ref "C1") (pin "2") (pinfunction "2_2") (pintype "passive"))
      (node (ref "C13") (pin "2") (pinfunction "2_2") (pintype "passive"))
      (node (ref "C14") (pin "2") (pinfunction "2_2") (pintype "passive"))
      (node (ref "C15") (pin "2") (pinfunction "2_2") (pintype "passive"))
      (node (ref "C16") (pin "1") (pinfunction "1_1") (pintype "passive"))
      (node (ref "C17") (pin "1") (pinfunction "1_1") (pintype "passive"))
      (node (ref "C18") (pin "2") (pinfunction "2_2") (pintype "passive"))
      (node (ref "C19") (pin "2") (pinfunction "2_2") (pintype "passive"))
      (node (ref "C2") (pin "2") (pinfunction "2_2") (pintype "passive"))
      (node (ref "C20") (pin "1") (pinfunction "1_1") (pintype "passive"))
      (node (ref "C21") (pin "1") (pinfunction "1_1") (pintype "passive"))
      (node (ref "C3") (pin "2") (pinfunction "2_2") (pintype "passive"))
      (node (ref "C5") (pin "1") (pinfunction "1_1") (pintype "passive"))
      (node (ref "C6") (pin "2") (pinfunction "2_2") (pintype "passive"))
      (node (ref "C8") (pin "1") (pinfunction "1_1") (pintype "passive"))
      (node (ref "IC1") (pin "3") (pinfunction "GND_3") (pintype "passive"))
      (node (ref "IC2") (pin "1") (pinfunction "GND_1") (pintype "power_in"))
      (node (ref "IC4") (pin "100") (pinfunction "GND8_100") (pintype "power_in"))
      (node (ref "IC4") (pin "21") (pinfunction "GND1_21") (pintype "power_in"))
      (node (ref "IC4") (pin "31") (pinfunction "GND2_31") (pintype "power_in"))
      (node (ref "IC4") (pin "44") (pinfunction "GND3_44") (pintype "power_in"))
      (node (ref "IC4") (pin "62") (pinfunction "GND4_62") (pintype "power_in"))
      (node (ref "IC4") (pin "69") (pinfunction "GND5_69") (pintype "power_in"))
      (node (ref "IC4") (pin "75") (pinfunction "GND6_75") (pintype "power_in"))
      (node (ref "IC4") (pin "84") (pinfunction "GND7_84") (pintype "power_in"))
      (node (ref "IC6") (pin "1") (pinfunction "OE_1") (pintype "input"))
      (node (ref "IC6") (pin "10") (pinfunction "OE_10") (pintype "input"))
      (node (ref "IC6") (pin "13") (pinfunction "OE_13") (pintype "input"))
      (node (ref "IC6") (pin "4") (pinfunction "OE_4") (pintype "input"))
      (node (ref "IC6") (pin "7") (pinfunction "GND_7") (pintype "power_in"))
      (node (ref "IC7") (pin "1") (pinfunction "GND_1") (pintype "bidirectional"))
      (node (ref "J1") (pin "5") (pinfunction "GND_5") (pintype "power_in"))
      (node (ref "J1") (pin "S1") (pinfunction "SHIELD_S1") (pintype "passive"))
      (node (ref "J1") (pin "S2") (pinfunction "SHIELD_S2") (pintype "passive"))
      (node (ref "J1") (pin "S3") (pinfunction "SHIELD_S3") (pintype "passive"))
      (node (ref "J1") (pin "S4") (pinfunction "SHIELD_S4") (pintype "passive"))
      (node (ref "J1") (pin "S5") (pinfunction "SHIELD_S5") (pintype "passive"))
      (node (ref "J1") (pin "S6") (pinfunction "SHIELD_S6") (pintype "passive"))
      (node (ref "JP2") (pin "2") (pinfunction "2_2") (pintype "passive"))
      (node (ref "JP6") (pin "6") (pinfunction "6_6") (pintype "passive"))
      (node (ref "LED2") (pin "2") (pinfunction "C_2") (pintype "bidirectional"))
      (node (ref "MICRO_SD1") (pin "6") (pinfunction "VSS_6") (pintype "power_in"))
      (node (ref "MICRO_SD1") (pin "MP1") (pinfunction "SHIELD_MP1") (pintype "power_in"))
      (node (ref "MICRO_SD1") (pin "MP2") (pinfunction "SHIELD_MP2") (pintype "power_in"))
      (node (ref "MICRO_SD1") (pin "MP3") (pinfunction "SHIELD_MP3") (pintype "power_in"))
      (node (ref "MICRO_SD1") (pin "MP4") (pinfunction "SHIELD_MP4") (pintype "power_in"))
      (node (ref "R10") (pin "1") (pinfunction "1_1") (pintype "passive"))
      (node (ref "R26") (pin "2") (pinfunction "2_2") (pintype "passive"))
      (node (ref "R8") (pin "1") (pinfunction "1_1") (pintype "passive"))
      (node (ref "R9") (pin "1") (pinfunction "1_1") (pintype "passive"))
      (node (ref "S1") (pin "1") (pinfunction "P_1") (pintype "passive"))
      (node (ref "U1") (pin "11") (pinfunction "GND_11") (pintype "power_in"))
      (node (ref "U1") (pin "32") (pinfunction "GND1_32") (pintype "power_in"))
      (node (ref "U1") (pin "62") (pinfunction "GND2_62") (pintype "power_in"))
      (node (ref "U1") (pin "81") (pinfunction "GND3_81") (pintype "power_in"))
      (node (ref "U1") (pin "99") (pinfunction "AGND_99") (pintype "power_in"))
      (node (ref "U2") (pin "16") (pinfunction "VSS_16") (pintype "output"))
    )
    (net (code "67") (name "LEDB") (class "Default")
      (node (ref "R3") (pin "1") (pinfunction "1_1") (pintype "passive"))
      (node (ref "U1") (pin "7") (pinfunction "(OC3C/INT5)PE5_7") (pintype "bidirectional"))
    )
    (net (code "68") (name "LEDG") (class "Default")
      (node (ref "R13") (pin "1") (pinfunction "1_1") (pintype "passive"))
      (node (ref "U1") (pin "1") (pinfunction "(OC0B)PG5_1") (pintype "bidirectional"))
    )
    (net (code "69") (name "LEDR") (class "Default")
      (node (ref "R2") (pin "1") (pinfunction "1_1") (pintype "passive"))
      (node (ref "U1") (pin "6") (pinfunction "(OC3B/INT4)PE4_6") (pintype "bidirectional"))
    )
    (net (code "70") (name "LE_IL") (class "Default")
      (node (ref "IC5") (pin "11") (pinfunction "C_11") (pintype "input"))
      (node (ref "U1") (pin "5") (pinfunction "(OC3A/AIN1)PE3_5") (pintype "bidirectional"))
    )
    (net (code "71") (name "LE_OL") (class "Default")
      (node (ref "IC4") (pin "72") (pinfunction "FB8MC15_72") (pintype "bidirectional"))
      (node (ref "IC9") (pin "11") (pinfunction "C_11") (pintype "input"))
    )
    (net (code "72") (name "MISO") (class "Default")
      (node (ref "JP6") (pin "1") (pinfunction "1_1") (pintype "passive"))
      (node (ref "R1") (pin "1") (pinfunction "1_1") (pintype "passive"))
      (node (ref "U1") (pin "22") (pinfunction "(MISO/PCINT3)PB3_22") (pintype "bidirectional"))
    )
    (net (code "73") (name "MOSI") (class "Default")
      (node (ref "JP6") (pin "4") (pinfunction "4_4") (pintype "passive"))
      (node (ref "R17") (pin "1") (pinfunction "1_1") (pintype "passive"))
      (node (ref "U1") (pin "21") (pinfunction "(MOSI/PCINT2)PB2_21") (pintype "bidirectional"))
    )
    (net (code "74") (name "Net-(IC4-FB5MC8)") (class "Default")
      (node (ref "IC4") (pin "39") (pinfunction "FB5MC8_39") (pintype "bidirectional"))
      (node (ref "JP1") (pin "2") (pinfunction "2_2") (pintype "passive"))
    )
    (net (code "75") (name "Net-(IC4-FB6MC2)") (class "Default")
      (node (ref "IC4") (pin "74") (pinfunction "FB6MC2_74") (pintype "bidirectional"))
      (node (ref "PAD8") (pin "1") (pinfunction "P_1") (pintype "passive"))
    )
    (net (code "76") (name "Net-(IC4-FB8MC6)") (class "Default")
      (node (ref "IC4") (pin "65") (pinfunction "FB8MC6_65") (pintype "bidirectional"))
      (node (ref "PAD2") (pin "1") (pinfunction "P_1") (pintype "passive"))
    )
    (net (code "77") (name "Net-(IC4-FB8MC8)") (class "Default")
      (node (ref "IC4") (pin "66") (pinfunction "FB8MC8_66") (pintype "bidirectional"))
      (node (ref "PAD3") (pin "1") (pinfunction "P_1") (pintype "passive"))
    )
    (net (code "78") (name "Net-(IC4-FB8MC9)") (class "Default")
      (node (ref "IC4") (pin "67") (pinfunction "FB8MC9_67") (pintype "bidirectional"))
      (node (ref "PAD4") (pin "1") (pinfunction "P_1") (pintype "passive"))
    )
    (net (code "79") (name "Net-(IC4-FB8MC11)") (class "Default")
      (node (ref "IC4") (pin "68") (pinfunction "FB8MC11_68") (pintype "bidirectional"))
      (node (ref "PAD5") (pin "1") (pinfunction "P_1") (pintype "passive"))
    )
    (net (code "80") (name "Net-(IC4-FB8MC12)") (class "Default")
      (node (ref "IC4") (pin "70") (pinfunction "FB8MC12_70") (pintype "bidirectional"))
      (node (ref "PAD7") (pin "1") (pinfunction "P_1") (pintype "passive"))
    )
    (net (code "81") (name "Net-(IC4-FB8MC17)") (class "Default")
      (node (ref "IC4") (pin "73") (pinfunction "FB8MC17_73") (pintype "bidirectional"))
      (node (ref "PAD6") (pin "1") (pinfunction "P_1") (pintype "passive"))
    )
    (net (code "82") (name "Net-(IC4-GCK3)") (class "Default")
      (node (ref "IC4") (pin "27") (pinfunction "GCK3_27") (pintype "bidirectional"))
      (node (ref "PAD1") (pin "1") (pinfunction "P_1") (pintype "passive"))
    )
    (net (code "83") (name "Net-(IC6A-I)") (class "Default")
      (node (ref "IC6") (pin "2") (pinfunction "I_2") (pintype "input"))
      (node (ref "R17") (pin "2") (pinfunction "2_2") (pintype "passive"))
    )
    (net (code "84") (name "Net-(IC6B-I)") (class "Default")
      (node (ref "IC6") (pin "5") (pinfunction "I_5") (pintype "input"))
      (node (ref "R18") (pin "2") (pinfunction "2_2") (pintype "passive"))
    )
    (net (code "85") (name "Net-(IC6C-I)") (class "Default")
      (node (ref "IC6") (pin "9") (pinfunction "I_9") (pintype "input"))
      (node (ref "R21") (pin "2") (pinfunction "2_2") (pintype "passive"))
    )
    (net (code "86") (name "Net-(IC6D-O)") (class "Default")
      (node (ref "IC6") (pin "11") (pinfunction "O_11") (pintype "tri_state"))
      (node (ref "R1") (pin "2") (pinfunction "2_2") (pintype "passive"))
    )
    (net (code "87") (name "Net-(IC7-DTR)") (class "Default")
      (node (ref "C9") (pin "2") (pinfunction "2_2") (pintype "passive"))
      (node (ref "IC7") (pin "13") (pinfunction "DTR_13") (pintype "bidirectional"))
      (node (ref "R26") (pin "1") (pinfunction "1_1") (pintype "passive"))
    )
    (net (code "88") (name "Net-(IC7-RX)") (class "Default")
      (node (ref "IC7") (pin "3") (pinfunction "RX_3") (pintype "bidirectional"))
      (node (ref "R23") (pin "2") (pinfunction "2_2") (pintype "passive"))
    )
    (net (code "89") (name "Net-(IC7-TX)") (class "Default")
      (node (ref "IC7") (pin "2") (pinfunction "TX_2") (pintype "bidirectional"))
      (node (ref "R22") (pin "2") (pinfunction "2_2") (pintype "passive"))
    )
    (net (code "90") (name "Net-(IC7-V3)") (class "Default")
      (node (ref "C8") (pin "2") (pinfunction "2_2") (pintype "passive"))
      (node (ref "IC7") (pin "4") (pinfunction "V3_4") (pintype "bidirectional"))
    )
    (net (code "91") (name "Net-(IC7-XI)") (class "Default")
      (node (ref "C20") (pin "2") (pinfunction "2_2") (pintype "passive"))
      (node (ref "IC7") (pin "7") (pinfunction "XI_7") (pintype "bidirectional"))
      (node (ref "Q2") (pin "3") (pinfunction "2_3") (pintype "passive"))
      (node (ref "R27") (pin "2") (pinfunction "2_2") (pintype "passive"))
    )
    (net (code "92") (name "Net-(IC7-XO)") (class "Default")
      (node (ref "C21") (pin "2") (pinfunction "2_2") (pintype "passive"))
      (node (ref "IC7") (pin "8") (pinfunction "XO_8") (pintype "bidirectional"))
      (node (ref "Q2") (pin "1") (pinfunction "1_1") (pintype "passive"))
      (node (ref "R27") (pin "1") (pinfunction "1_1") (pintype "passive"))
    )
    (net (code "93") (name "Net-(J1-D+)") (class "Default")
      (node (ref "J1") (pin "3") (pinfunction "D+_3") (pintype "bidirectional"))
      (node (ref "R29") (pin "2") (pinfunction "2_2") (pintype "passive"))
    )
    (net (code "94") (name "Net-(J1-D-)") (class "Default")
      (node (ref "J1") (pin "2") (pinfunction "D-_2") (pintype "bidirectional"))
      (node (ref "R28") (pin "2") (pinfunction "2_2") (pintype "passive"))
    )
    (net (code "95") (name "Net-(LED1-PadA)") (class "Default")
      (node (ref "LED1") (pin "A") (pinfunction "A_A") (pintype "passive"))
      (node (ref "R11") (pin "2") (pinfunction "2_2") (pintype "passive"))
    )
    (net (code "96") (name "Net-(LED2-BLU)") (class "Default")
      (node (ref "LED2") (pin "4") (pinfunction "BLU_4") (pintype "bidirectional"))
      (node (ref "R3") (pin "2") (pinfunction "2_2") (pintype "passive"))
    )
    (net (code "97") (name "Net-(LED2-GRN)") (class "Default")
      (node (ref "LED2") (pin "3") (pinfunction "GRN_3") (pintype "bidirectional"))
      (node (ref "R13") (pin "2") (pinfunction "2_2") (pintype "passive"))
    )
    (net (code "98") (name "Net-(LED2-RED)") (class "Default")
      (node (ref "LED2") (pin "1") (pinfunction "RED_1") (pintype "bidirectional"))
      (node (ref "R2") (pin "2") (pinfunction "2_2") (pintype "passive"))
    )
    (net (code "99") (name "Net-(MICRO_SD1-DAT0)") (class "Default")
      (node (ref "MICRO_SD1") (pin "7") (pinfunction "DAT0_7") (pintype "bidirectional"))
      (node (ref "R20") (pin "2") (pinfunction "2_2") (pintype "passive"))
    )
    (net (code "100") (name "Net-(Q1-2)") (class "Default")
      (node (ref "C16") (pin "2") (pinfunction "2_2") (pintype "passive"))
      (node (ref "Q1") (pin "3") (pinfunction "2_3") (pintype "passive"))
      (node (ref "R19") (pin "2") (pinfunction "2_2") (pintype "passive"))
      (node (ref "U1") (pin "33") (pinfunction "XTAL2_33") (pintype "output"))
    )
    (net (code "101") (name "Net-(U1-XTAL1)") (class "Default")
      (node (ref "C17") (pin "2") (pinfunction "2_2") (pintype "passive"))
      (node (ref "Q1") (pin "1") (pinfunction "1_1") (pintype "passive"))
      (node (ref "R19") (pin "1") (pinfunction "1_1") (pintype "passive"))
      (node (ref "U1") (pin "34") (pinfunction "XTAL1_34") (pintype "input"))
    )
    (net (code "102") (name "O0") (class "Default")
      (node (ref "IC5") (pin "2") (pinfunction "1D_2") (pintype "input"))
      (node (ref "U1") (pin "89") (pinfunction "PK0(ADC8/PCINT16)_89") (pintype "bidirectional"))
    )
    (net (code "103") (name "O1") (class "Default")
      (node (ref "IC5") (pin "3") (pinfunction "2D_3") (pintype "input"))
      (node (ref "U1") (pin "88") (pinfunction "PK1(ADC9/PCINT17)_88") (pintype "bidirectional"))
    )
    (net (code "104") (name "O2") (class "Default")
      (node (ref "IC5") (pin "4") (pinfunction "3D_4") (pintype "input"))
      (node (ref "U1") (pin "87") (pinfunction "PK2(ADC10/PCINT18)_87") (pintype "bidirectional"))
    )
    (net (code "105") (name "O3") (class "Default")
      (node (ref "IC5") (pin "5") (pinfunction "4D_5") (pintype "input"))
      (node (ref "U1") (pin "86") (pinfunction "PK3(ADC11/PCINT19)_86") (pintype "bidirectional"))
    )
    (net (code "106") (name "O4") (class "Default")
      (node (ref "IC5") (pin "6") (pinfunction "5D_6") (pintype "input"))
      (node (ref "U1") (pin "85") (pinfunction "PK4(ADC12/PCINT20)_85") (pintype "bidirectional"))
    )
    (net (code "107") (name "O5") (class "Default")
      (node (ref "IC5") (pin "7") (pinfunction "6D_7") (pintype "input"))
      (node (ref "U1") (pin "84") (pinfunction "PK5(ADC13/PCINT21)_84") (pintype "bidirectional"))
    )
    (net (code "108") (name "O6") (class "Default")
      (node (ref "IC5") (pin "8") (pinfunction "7D_8") (pintype "input"))
      (node (ref "U1") (pin "83") (pinfunction "PK6(ADC14/PCINT22)_83") (pintype "bidirectional"))
    )
    (net (code "109") (name "O7") (class "Default")
      (node (ref "IC5") (pin "9") (pinfunction "8D_9") (pintype "input"))
      (node (ref "U1") (pin "82") (pinfunction "PK7(ADC15/PCINT23)_82") (pintype "bidirectional"))
    )
    (net (code "110") (name "OE_OL") (class "Default")
      (node (ref "IC9") (pin "1") (pinfunction "OC_1") (pintype "input"))
      (node (ref "U1") (pin "13") (pinfunction "PH1(TXD2)_13") (pintype "bidirectional"))
    )
    (net (code "111") (name "PAGE_A8") (class "Default")
      (node (ref "IC4") (pin "80") (pinfunction "FB6MC11_80") (pintype "bidirectional"))
      (node (ref "U1") (pin "41") (pinfunction "PL6_41") (pintype "bidirectional"))
    )
    (net (code "112") (name "RD+") (class "Default")
      (node (ref "IC7") (pin "5") (pinfunction "D+_5") (pintype "bidirectional"))
      (node (ref "R29") (pin "1") (pinfunction "1_1") (pintype "passive"))
    )
    (net (code "113") (name "RD-") (class "Default")
      (node (ref "IC7") (pin "6") (pinfunction "D-_6") (pintype "bidirectional"))
      (node (ref "R28") (pin "1") (pinfunction "1_1") (pintype "passive"))
    )
    (net (code "114") (name "RESET") (class "Default")
      (node (ref "C5") (pin "2") (pinfunction "2_2") (pintype "passive"))
      (node (ref "C9") (pin "1") (pinfunction "1_1") (pintype "passive"))
      (node (ref "D1") (pin "A") (pinfunction "A_A") (pintype "passive"))
      (node (ref "JP6") (pin "5") (pinfunction "5_5") (pintype "passive"))
      (node (ref "R15") (pin "1") (pinfunction "1_1") (pintype "passive"))
      (node (ref "S1") (pin "2") (pinfunction "S_2") (pintype "passive"))
      (node (ref "U1") (pin "30") (pinfunction "RESET_30") (pintype "input"))
    )
    (net (code "115") (name "ROM_WR_EN") (class "Default")
      (node (ref "IC4") (pin "79") (pinfunction "FB6MC9_79") (pintype "bidirectional"))
      (node (ref "U1") (pin "36") (pinfunction "PL1(ICP5)_36") (pintype "bidirectional"))
    )
    (net (code "116") (name "RST_CTRL_REG") (class "Default")
      (node (ref "IC4") (pin "82") (pinfunction "FB6MC14_82") (pintype "bidirectional"))
      (node (ref "U1") (pin "26") (pinfunction "(OC0A/OC1C/PCINT7)PB7_26") (pintype "bidirectional"))
    )
    (net (code "117") (name "RST_DATA_REG") (class "Default")
      (node (ref "IC4") (pin "81") (pinfunction "FB6MC12_81") (pintype "bidirectional"))
      (node (ref "U1") (pin "63") (pinfunction "PJ0(RXD3/PCINT9)_63") (pintype "bidirectional"))
    )
    (net (code "118") (name "RX0") (class "Default")
      (node (ref "R23") (pin "1") (pinfunction "1_1") (pintype "passive"))
      (node (ref "U1") (pin "3") (pinfunction "(TXD0)PE1_3") (pintype "bidirectional"))
    )
    (net (code "119") (name "SCK_LLS") (class "Default")
      (node (ref "IC6") (pin "6") (pinfunction "O_6") (pintype "tri_state"))
      (node (ref "MICRO_SD1") (pin "5") (pinfunction "CLK_5") (pintype "bidirectional"))
    )
    (net (code "120") (name "SCLK") (class "Default")
      (node (ref "JP6") (pin "3") (pinfunction "3_3") (pintype "passive"))
      (node (ref "R18") (pin "1") (pinfunction "1_1") (pintype "passive"))
      (node (ref "U1") (pin "20") (pinfunction "(SCK/PCINT1)PB1_20") (pintype "bidirectional"))
    )
    (net (code "121") (name "SD_LED") (class "Default")
      (node (ref "LED1") (pin "K") (pinfunction "C_K") (pintype "passive"))
      (node (ref "U1") (pin "37") (pinfunction "PL2(T5)_37") (pintype "bidirectional"))
    )
    (net (code "122") (name "SEL_128CHARS") (class "Default")
      (node (ref "IC4") (pin "78") (pinfunction "FB6MC8_78") (pintype "bidirectional"))
      (node (ref "U1") (pin "35") (pinfunction "PL0(ICP4)_35") (pintype "bidirectional"))
    )
    (net (code "123") (name "SPARE1") (class "Default")
      (node (ref "IC4") (pin "77") (pinfunction "FB6MC6_77") (pintype "bidirectional"))
      (node (ref "U1") (pin "38") (pinfunction "PL3(OC5A)_38") (pintype "bidirectional"))
    )
    (net (code "124") (name "SS_SD") (class "Default")
      (node (ref "R21") (pin "1") (pinfunction "1_1") (pintype "passive"))
      (node (ref "U1") (pin "19") (pinfunction "(SS/PCINT0)PB0_19") (pintype "bidirectional"))
    )
    (net (code "125") (name "TCK") (class "Default")
      (node (ref "IC4") (pin "48") (pinfunction "TCK_48") (pintype "passive"))
      (node (ref "JP3") (pin "1") (pinfunction "1_1") (pintype "passive"))
      (node (ref "R7") (pin "2") (pinfunction "2_2") (pintype "passive"))
      (node (ref "R8") (pin "2") (pinfunction "2_2") (pintype "passive"))
    )
    (net (code "126") (name "TCK'") (class "Default")
      (node (ref "R7") (pin "1") (pinfunction "1_1") (pintype "passive"))
      (node (ref "U1") (pin "24") (pinfunction "(OC1A/PCINT5)PB5_24") (pintype "bidirectional"))
    )
    (net (code "127") (name "TDI") (class "Default")
      (node (ref "IC4") (pin "45") (pinfunction "TDI_45") (pintype "passive"))
      (node (ref "JP3") (pin "3") (pinfunction "3_3") (pintype "passive"))
      (node (ref "R5") (pin "2") (pinfunction "2_2") (pintype "passive"))
      (node (ref "R9") (pin "2") (pinfunction "2_2") (pintype "passive"))
    )
    (net (code "128") (name "TDI'") (class "Default")
      (node (ref "R5") (pin "1") (pinfunction "1_1") (pintype "passive"))
      (node (ref "U1") (pin "18") (pinfunction "PH6(OC2B)_18") (pintype "bidirectional"))
    )
    (net (code "129") (name "TDO") (class "Default")
      (node (ref "IC4") (pin "83") (pinfunction "TDO_83") (pintype "passive"))
      (node (ref "JP3") (pin "2") (pinfunction "2_2") (pintype "passive"))
      (node (ref "R6") (pin "2") (pinfunction "2_2") (pintype "passive"))
    )
    (net (code "130") (name "TDO'") (class "Default")
      (node (ref "R6") (pin "1") (pinfunction "1_1") (pintype "passive"))
      (node (ref "U1") (pin "17") (pinfunction "PH5(OC4C)_17") (pintype "bidirectional"))
    )
    (net (code "131") (name "TMS") (class "Default")
      (node (ref "IC4") (pin "47") (pinfunction "TMS_47") (pintype "passive"))
      (node (ref "JP3") (pin "4") (pinfunction "4_4") (pintype "passive"))
      (node (ref "R10") (pin "2") (pinfunction "2_2") (pintype "passive"))
      (node (ref "R4") (pin "2") (pinfunction "2_2") (pintype "passive"))
    )
    (net (code "132") (name "TMS'") (class "Default")
      (node (ref "R4") (pin "1") (pinfunction "1_1") (pintype "passive"))
      (node (ref "U1") (pin "23") (pinfunction "(OC2A/PCINT4)PB4_23") (pintype "bidirectional"))
    )
    (net (code "133") (name "TX0") (class "Default")
      (node (ref "R22") (pin "1") (pinfunction "1_1") (pintype "passive"))
      (node (ref "U1") (pin "2") (pinfunction "(RXD0/PCIN8)PE0_2") (pintype "bidirectional"))
    )
    (net (code "134") (name "VCC") (class "Default")
      (node (ref "C1") (pin "1") (pinfunction "1_1") (pintype "passive"))
      (node (ref "C13") (pin "1") (pinfunction "1_1") (pintype "passive"))
      (node (ref "C14") (pin "1") (pinfunction "1_1") (pintype "passive"))
      (node (ref "C15") (pin "1") (pinfunction "1_1") (pintype "passive"))
      (node (ref "C19") (pin "1") (pinfunction "1_1") (pintype "passive"))
      (node (ref "C2") (pin "1") (pinfunction "1_1") (pintype "passive"))
      (node (ref "C3") (pin "1") (pinfunction "1_1") (pintype "passive"))
      (node (ref "D1") (pin "C") (pinfunction "C_C") (pintype "passive"))
      (node (ref "IC1") (pin "2") (pinfunction "VO_2") (pintype "passive"))
      (node (ref "IC2") (pin "3") (pinfunction "VIN_3") (pintype "input"))
      (node (ref "IC3") (pin "12") (pinfunction "I_12") (pintype "input"))
      (node (ref "IC3") (pin "13") (pinfunction "OE_13") (pintype "input"))
      (node (ref "IC3") (pin "2") (pinfunction "I_2") (pintype "input"))
      (node (ref "IC3") (pin "5") (pinfunction "I_5") (pintype "input"))
      (node (ref "IC7") (pin "16") (pinfunction "VCC_16") (pintype "bidirectional"))
      (node (ref "J1") (pin "1") (pinfunction "VBUS_1") (pintype "power_in"))
      (node (ref "JP6") (pin "2") (pinfunction "2_2") (pintype "passive"))
      (node (ref "R11") (pin "1") (pinfunction "1_1") (pintype "passive"))
      (node (ref "R15") (pin "2") (pinfunction "2_2") (pintype "passive"))
      (node (ref "U1") (pin "10") (pinfunction "VCC_10") (pintype "power_in"))
      (node (ref "U1") (pin "100") (pinfunction "AVCC_100") (pintype "power_in"))
      (node (ref "U1") (pin "31") (pinfunction "VCC1_31") (pintype "power_in"))
      (node (ref "U1") (pin "61") (pinfunction "VCC2_61") (pintype "power_in"))
      (node (ref "U1") (pin "80") (pinfunction "VCC3_80") (pintype "power_in"))
      (node (ref "U2") (pin "32") (pinfunction "VCC_32") (pintype "power_in"))
    )
    (net (code "135") (name "unconnected-(IC3D-O-Pad11)") (class "Default")
      (node (ref "IC3") (pin "11") (pinfunction "O_11") (pintype "tri_state"))
    )
    (net (code "136") (name "unconnected-(IC7-CTS-Pad9)") (class "Default")
      (node (ref "IC7") (pin "9") (pinfunction "CTS_9") (pintype "bidirectional"))
    )
    (net (code "137") (name "unconnected-(IC7-DCD-Pad12)") (class "Default")
      (node (ref "IC7") (pin "12") (pinfunction "DCD_12") (pintype "bidirectional"))
    )
    (net (code "138") (name "unconnected-(IC7-DSR-Pad10)") (class "Default")
      (node (ref "IC7") (pin "10") (pinfunction "DSR_10") (pintype "bidirectional"))
    )
    (net (code "139") (name "unconnected-(IC7-RI-Pad11)") (class "Default")
      (node (ref "IC7") (pin "11") (pinfunction "RI_11") (pintype "bidirectional"))
    )
    (net (code "140") (name "unconnected-(IC7-RS232-Pad15)") (class "Default")
      (node (ref "IC7") (pin "15") (pinfunction "RS232_15") (pintype "bidirectional"))
    )
    (net (code "141") (name "unconnected-(IC7-RTS-Pad14)") (class "Default")
      (node (ref "IC7") (pin "14") (pinfunction "RTS_14") (pintype "bidirectional"))
    )
    (net (code "142") (name "unconnected-(J1-ID-Pad4)") (class "Default")
      (node (ref "J1") (pin "4") (pinfunction "ID_4") (pintype "bidirectional"))
    )
    (net (code "143") (name "unconnected-(MICRO_SD1-CD-PadCD1)") (class "Default")
      (node (ref "MICRO_SD1") (pin "CD1") (pinfunction "CD_CD1") (pintype "passive"))
    )
    (net (code "144") (name "unconnected-(MICRO_SD1-DAT1-Pad8)") (class "Default")
      (node (ref "MICRO_SD1") (pin "8") (pinfunction "DAT1_8") (pintype "bidirectional"))
    )
    (net (code "145") (name "unconnected-(MICRO_SD1-DAT2-Pad1)") (class "Default")
      (node (ref "MICRO_SD1") (pin "1") (pinfunction "DAT2_1") (pintype "bidirectional"))
    )
    (net (code "146") (name "unconnected-(U1-(CLKO{slash}ICP3{slash}INT7)PE7-Pad9)") (class "Default")
      (node (ref "U1") (pin "9") (pinfunction "(CLKO/ICP3/INT7)PE7_9") (pintype "bidirectional"))
    )
    (net (code "147") (name "unconnected-(U1-(ICP1)PD4-Pad47)") (class "Default")
      (node (ref "U1") (pin "47") (pinfunction "(ICP1)PD4_47") (pintype "bidirectional"))
    )
    (net (code "148") (name "unconnected-(U1-(T1)PD6-Pad49)") (class "Default")
      (node (ref "U1") (pin "49") (pinfunction "(T1)PD6_49") (pintype "bidirectional"))
    )
    (net (code "149") (name "unconnected-(U1-(T3{slash}INT6)PE6-Pad8)") (class "Default")
      (node (ref "U1") (pin "8") (pinfunction "(T3/INT6)PE6_8") (pintype "bidirectional"))
    )
    (net (code "150") (name "unconnected-(U1-(TOSC1)PG4-Pad29)") (class "Default")
      (node (ref "U1") (pin "29") (pinfunction "(TOSC1)PG4_29") (pintype "bidirectional"))
    )
    (net (code "151") (name "unconnected-(U1-(TOSC2)PG3-Pad28)") (class "Default")
      (node (ref "U1") (pin "28") (pinfunction "(TOSC2)PG3_28") (pintype "bidirectional"))
    )
    (net (code "152") (name "unconnected-(U1-(XCK0{slash}AIN0)PE2-Pad4)") (class "Default")
      (node (ref "U1") (pin "4") (pinfunction "(XCK0/AIN0)PE2_4") (pintype "bidirectional"))
    )
    (net (code "153") (name "unconnected-(U1-(XCK1)PD5-Pad48)") (class "Default")
      (node (ref "U1") (pin "48") (pinfunction "(XCK1)PD5_48") (pintype "bidirectional"))
    )
    (net (code "154") (name "unconnected-(U1-PH2(XCK2)-Pad14)") (class "Default")
      (node (ref "U1") (pin "14") (pinfunction "PH2(XCK2)_14") (pintype "bidirectional"))
    )
    (net (code "155") (name "unconnected-(U1-PH7(T4)-Pad27)") (class "Default")
      (node (ref "U1") (pin "27") (pinfunction "PH7(T4)_27") (pintype "bidirectional"))
    )
    (net (code "156") (name "unconnected-(U1-PJ2(XCK3{slash}PCINT11)-Pad65)") (class "Default")
      (node (ref "U1") (pin "65") (pinfunction "PJ2(XCK3/PCINT11)_65") (pintype "bidirectional"))
    )
    (net (code "157") (name "unconnected-(U1-PJ3(PCINT12)-Pad66)") (class "Default")
      (node (ref "U1") (pin "66") (pinfunction "PJ3(PCINT12)_66") (pintype "bidirectional"))
    )
    (net (code "158") (name "unconnected-(U1-PJ4(PCINT13)-Pad67)") (class "Default")
      (node (ref "U1") (pin "67") (pinfunction "PJ4(PCINT13)_67") (pintype "bidirectional"))
    )
    (net (code "159") (name "unconnected-(U1-PJ5(PCINT14)-Pad68)") (class "Default")
      (node (ref "U1") (pin "68") (pinfunction "PJ5(PCINT14)_68") (pintype "bidirectional"))
    )
    (net (code "160") (name "unconnected-(U1-PJ6(PCINT15)-Pad69)") (class "Default")
      (node (ref "U1") (pin "69") (pinfunction "PJ6(PCINT15)_69") (pintype "bidirectional"))
    )
    (net (code "161") (name "unconnected-(U1-PJ7-Pad79)") (class "Default")
      (node (ref "U1") (pin "79") (pinfunction "PJ7_79") (pintype "bidirectional"))
    )
    (net (code "162") (name "{slash}BUSAK") (class "Default")
      (node (ref "18A") (pin "1") (pinfunction "P_1") (pintype "passive"))
      (node (ref "IC4") (pin "54") (pinfunction "FB7MC8_54") (pintype "bidirectional"))
    )
    (net (code "163") (name "{slash}BUSRQ") (class "Default")
      (node (ref "20A") (pin "1") (pinfunction "P_1") (pintype "passive"))
      (node (ref "IC4") (pin "59") (pinfunction "FB7MC14_59") (pintype "bidirectional"))
    )
    (net (code "164") (name "{slash}CLOCK") (class "Default")
      (node (ref "6B") (pin "1") (pinfunction "P_1") (pintype "passive"))
      (node (ref "IC4") (pin "22") (pinfunction "GCK1_22") (pintype "bidirectional"))
    )
    (net (code "165") (name "{slash}HALT") (class "Default")
      (node (ref "13A") (pin "1") (pinfunction "P_1") (pintype "passive"))
      (node (ref "JP1") (pin "1") (pinfunction "1_1") (pintype "passive"))
    )
    (net (code "166") (name "{slash}IORQ") (class "Default")
      (node (ref "15A") (pin "1") (pinfunction "P_1") (pintype "passive"))
      (node (ref "IC4") (pin "43") (pinfunction "FB5MC14_43") (pintype "bidirectional"))
    )
    (net (code "167") (name "{slash}M1") (class "Default")
      (node (ref "22A") (pin "1") (pinfunction "P_1") (pintype "passive"))
      (node (ref "IC4") (pin "61") (pinfunction "FB7MC17_61") (pintype "bidirectional"))
    )
    (net (code "168") (name "{slash}MEM_CE") (class "Default")
      (node (ref "IC4") (pin "97") (pinfunction "FB4MC17_97") (pintype "bidirectional"))
      (node (ref "U1") (pin "50") (pinfunction "(T0)PD7_50") (pintype "bidirectional"))
      (node (ref "U2") (pin "22") (pinfunction "CE_22") (pintype "input"))
    )
    (net (code "169") (name "{slash}MEM_OE") (class "Default")
      (node (ref "IC4") (pin "12") (pinfunction "FB1MC3_12") (pintype "bidirectional"))
      (node (ref "U1") (pin "52") (pinfunction "(RD)PG1_52") (pintype "bidirectional"))
      (node (ref "U2") (pin "24") (pinfunction "OE_24") (pintype "input"))
    )
    (net (code "170") (name "{slash}MREQ") (class "Default")
      (node (ref "14A") (pin "1") (pinfunction "P_1") (pintype "passive"))
      (node (ref "IC4") (pin "41") (pinfunction "FB5MC11_41") (pintype "bidirectional"))
    )
    (net (code "171") (name "{slash}NMI") (class "Default")
      (node (ref "12A") (pin "1") (pinfunction "P_1") (pintype "passive"))
      (node (ref "IC4") (pin "36") (pinfunction "FB5MC5_36") (pintype "bidirectional"))
    )
    (net (code "172") (name "{slash}OE_CTRL_CLOCK") (class "Default")
      (node (ref "IC3") (pin "10") (pinfunction "OE_10") (pintype "input"))
      (node (ref "IC4") (pin "10") (pinfunction "FB2MC17_10") (pintype "bidirectional"))
    )
    (net (code "173") (name "{slash}OE_IL") (class "Default")
      (node (ref "IC4") (pin "15") (pinfunction "FB1MC8_15") (pintype "bidirectional"))
      (node (ref "IC5") (pin "1") (pinfunction "OC_1") (pintype "input"))
    )
    (net (code "174") (name "{slash}OE_RAMCS") (class "Default")
      (node (ref "IC3") (pin "4") (pinfunction "OE_4") (pintype "input"))
      (node (ref "IC4") (pin "17") (pinfunction "FB1MC11_17") (pintype "bidirectional"))
    )
    (net (code "175") (name "{slash}OE_ROMCS") (class "Default")
      (node (ref "IC3") (pin "1") (pinfunction "OE_1") (pintype "input"))
      (node (ref "IC4") (pin "14") (pinfunction "FB1MC6_14") (pintype "bidirectional"))
    )
    (net (code "176") (name "{slash}RAMCS") (class "Default")
      (node (ref "2A") (pin "1") (pinfunction "P_1") (pintype "passive"))
      (node (ref "IC3") (pin "6") (pinfunction "O_6") (pintype "tri_state"))
    )
    (net (code "177") (name "{slash}RD") (class "Default")
      (node (ref "16A") (pin "1") (pinfunction "P_1") (pintype "passive"))
      (node (ref "IC4") (pin "49") (pinfunction "FB5MC17_49") (pintype "bidirectional"))
    )
    (net (code "178") (name "{slash}RESET") (class "Default")
      (node (ref "21A") (pin "1") (pinfunction "P_1") (pintype "passive"))
      (node (ref "IC4") (pin "71") (pinfunction "FB8MC14_71") (pintype "bidirectional"))
      (node (ref "U1") (pin "15") (pinfunction "PH3(OC4A)_15") (pintype "bidirectional"))
    )
    (net (code "179") (name "{slash}RFSH") (class "Default")
      (node (ref "23A") (pin "1") (pinfunction "P_1") (pintype "passive"))
      (node (ref "IC4") (pin "64") (pinfunction "FB8MC5_64") (pintype "bidirectional"))
    )
    (net (code "180") (name "{slash}ROMCS") (class "Default")
      (node (ref "23B") (pin "1") (pinfunction "P_1") (pintype "passive"))
      (node (ref "IC3") (pin "3") (pinfunction "O_3") (pintype "tri_state"))
    )
    (net (code "181") (name "{slash}WAIT") (class "Default")
      (node (ref "19A") (pin "1") (pinfunction "P_1") (pintype "passive"))
      (node (ref "IC4") (pin "56") (pinfunction "FB7MC11_56") (pintype "bidirectional"))
      (node (ref "U1") (pin "42") (pinfunction "PL7_42") (pintype "bidirectional"))
    )
    (net (code "182") (name "{slash}WR") (class "Default")
      (node (ref "17A") (pin "1") (pinfunction "P_1") (pintype "passive"))
      (node (ref "IC4") (pin "52") (pinfunction "FB7MC5_52") (pintype "bidirectional"))
    )
    (net (code "183") (name "{slash}WR'") (class "Default")
      (node (ref "IC4") (pin "13") (pinfunction "FB1MC5_13") (pintype "bidirectional"))
      (node (ref "U1") (pin "51") (pinfunction "(WR)PG0_51") (pintype "bidirectional"))
      (node (ref "U2") (pin "29") (pinfunction "WE_29") (pintype "input"))
    )
  )
)
